# DRM-X_voice_split_resistors.net
KiCad netlist of a schematic drawn in EAGLE
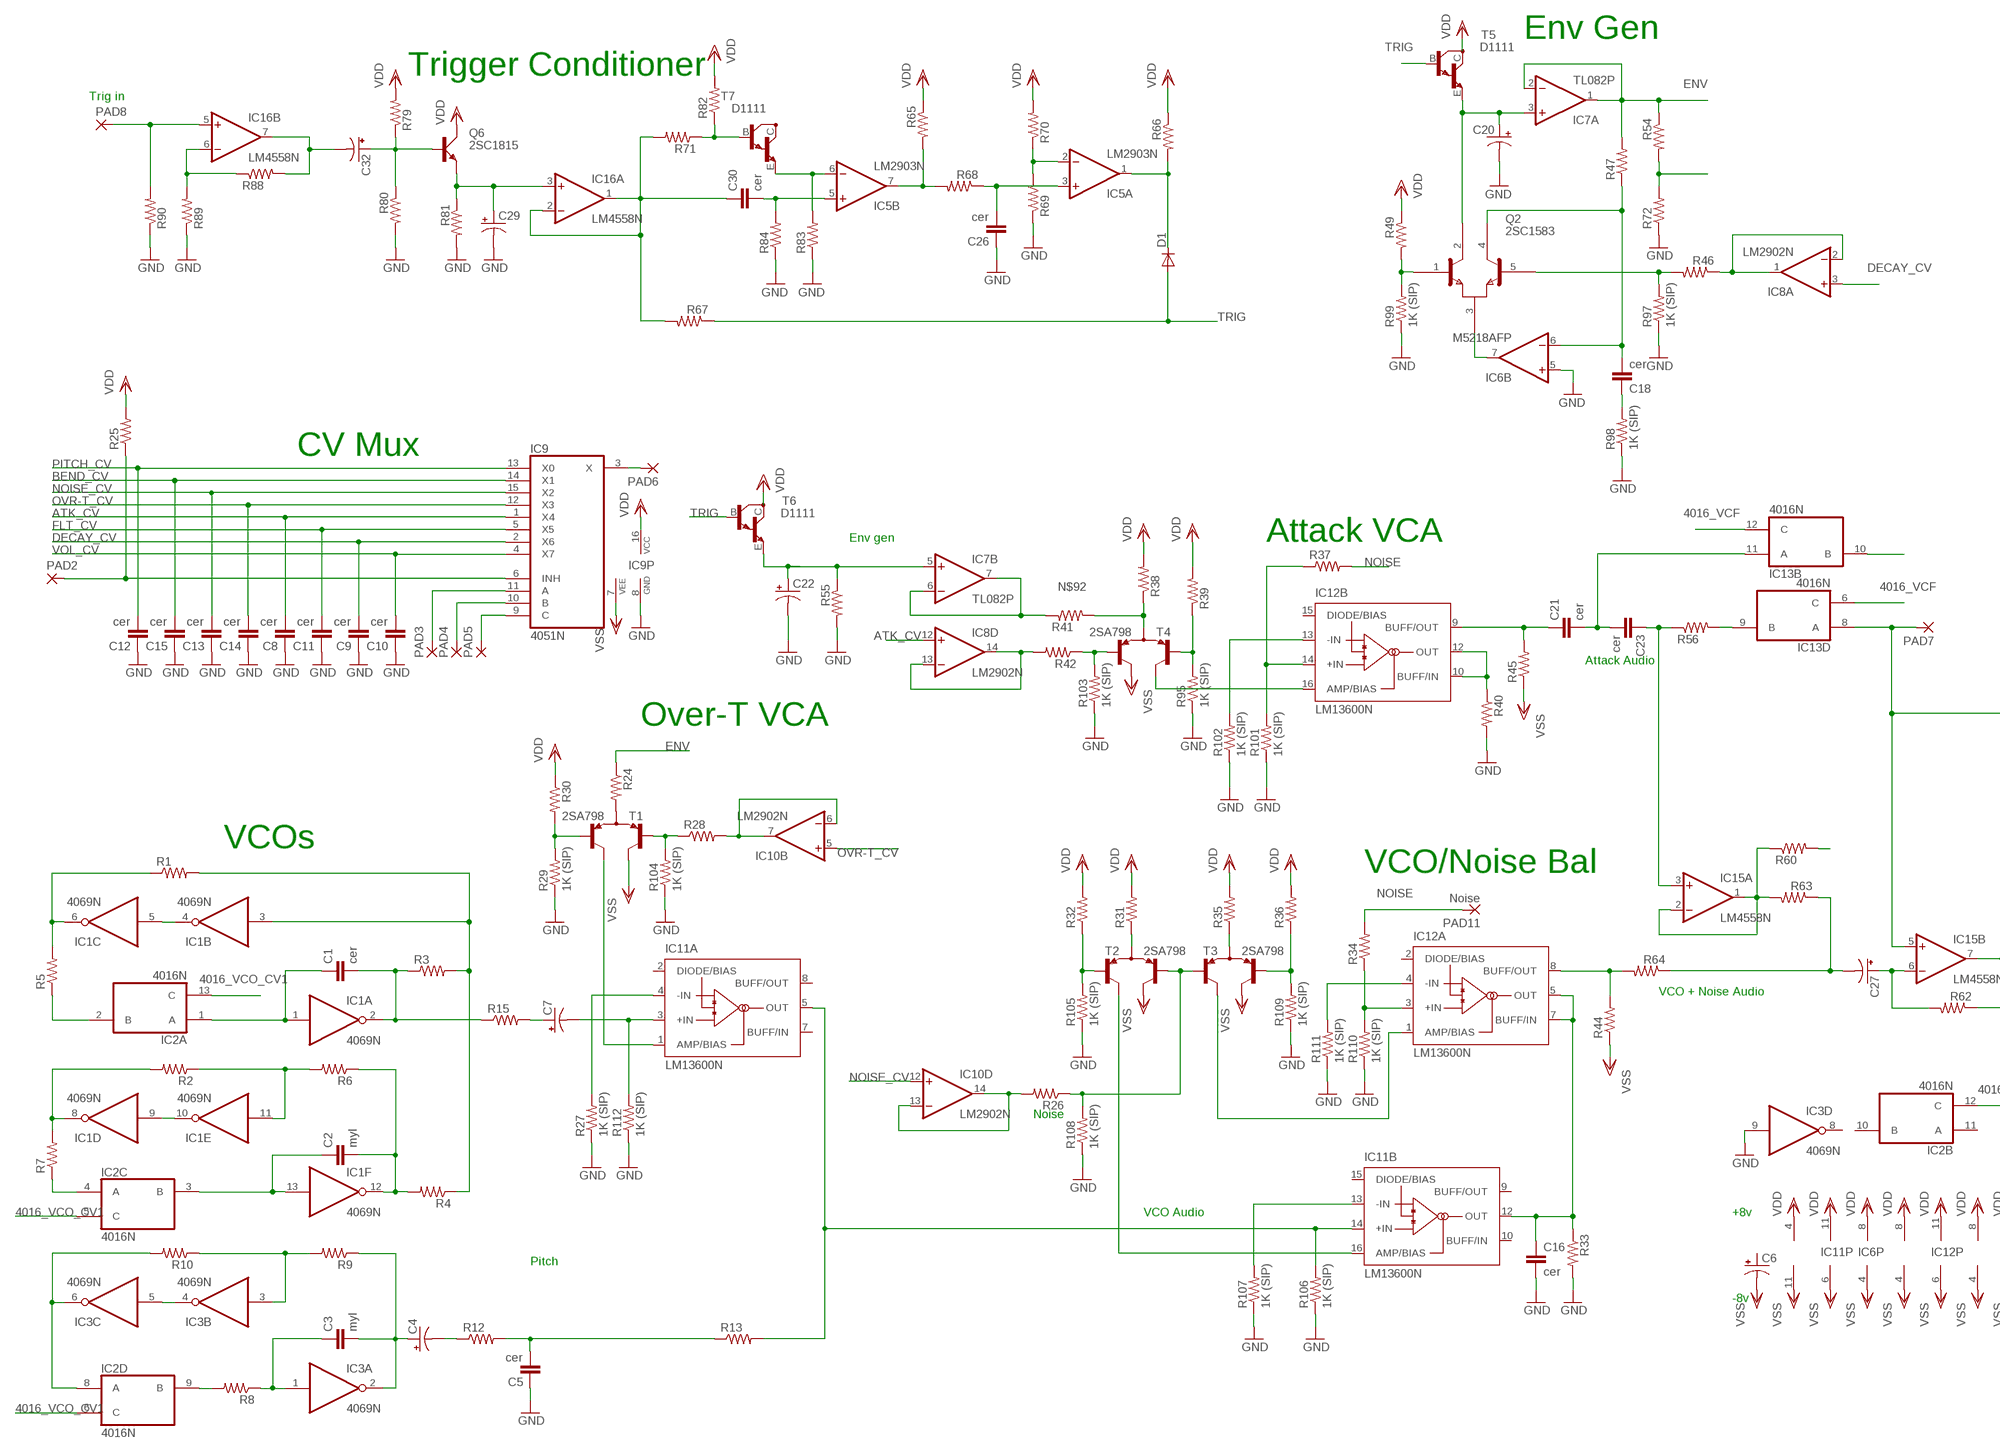
[diagram p0: schematic, sheet 1, part 1 of 2]
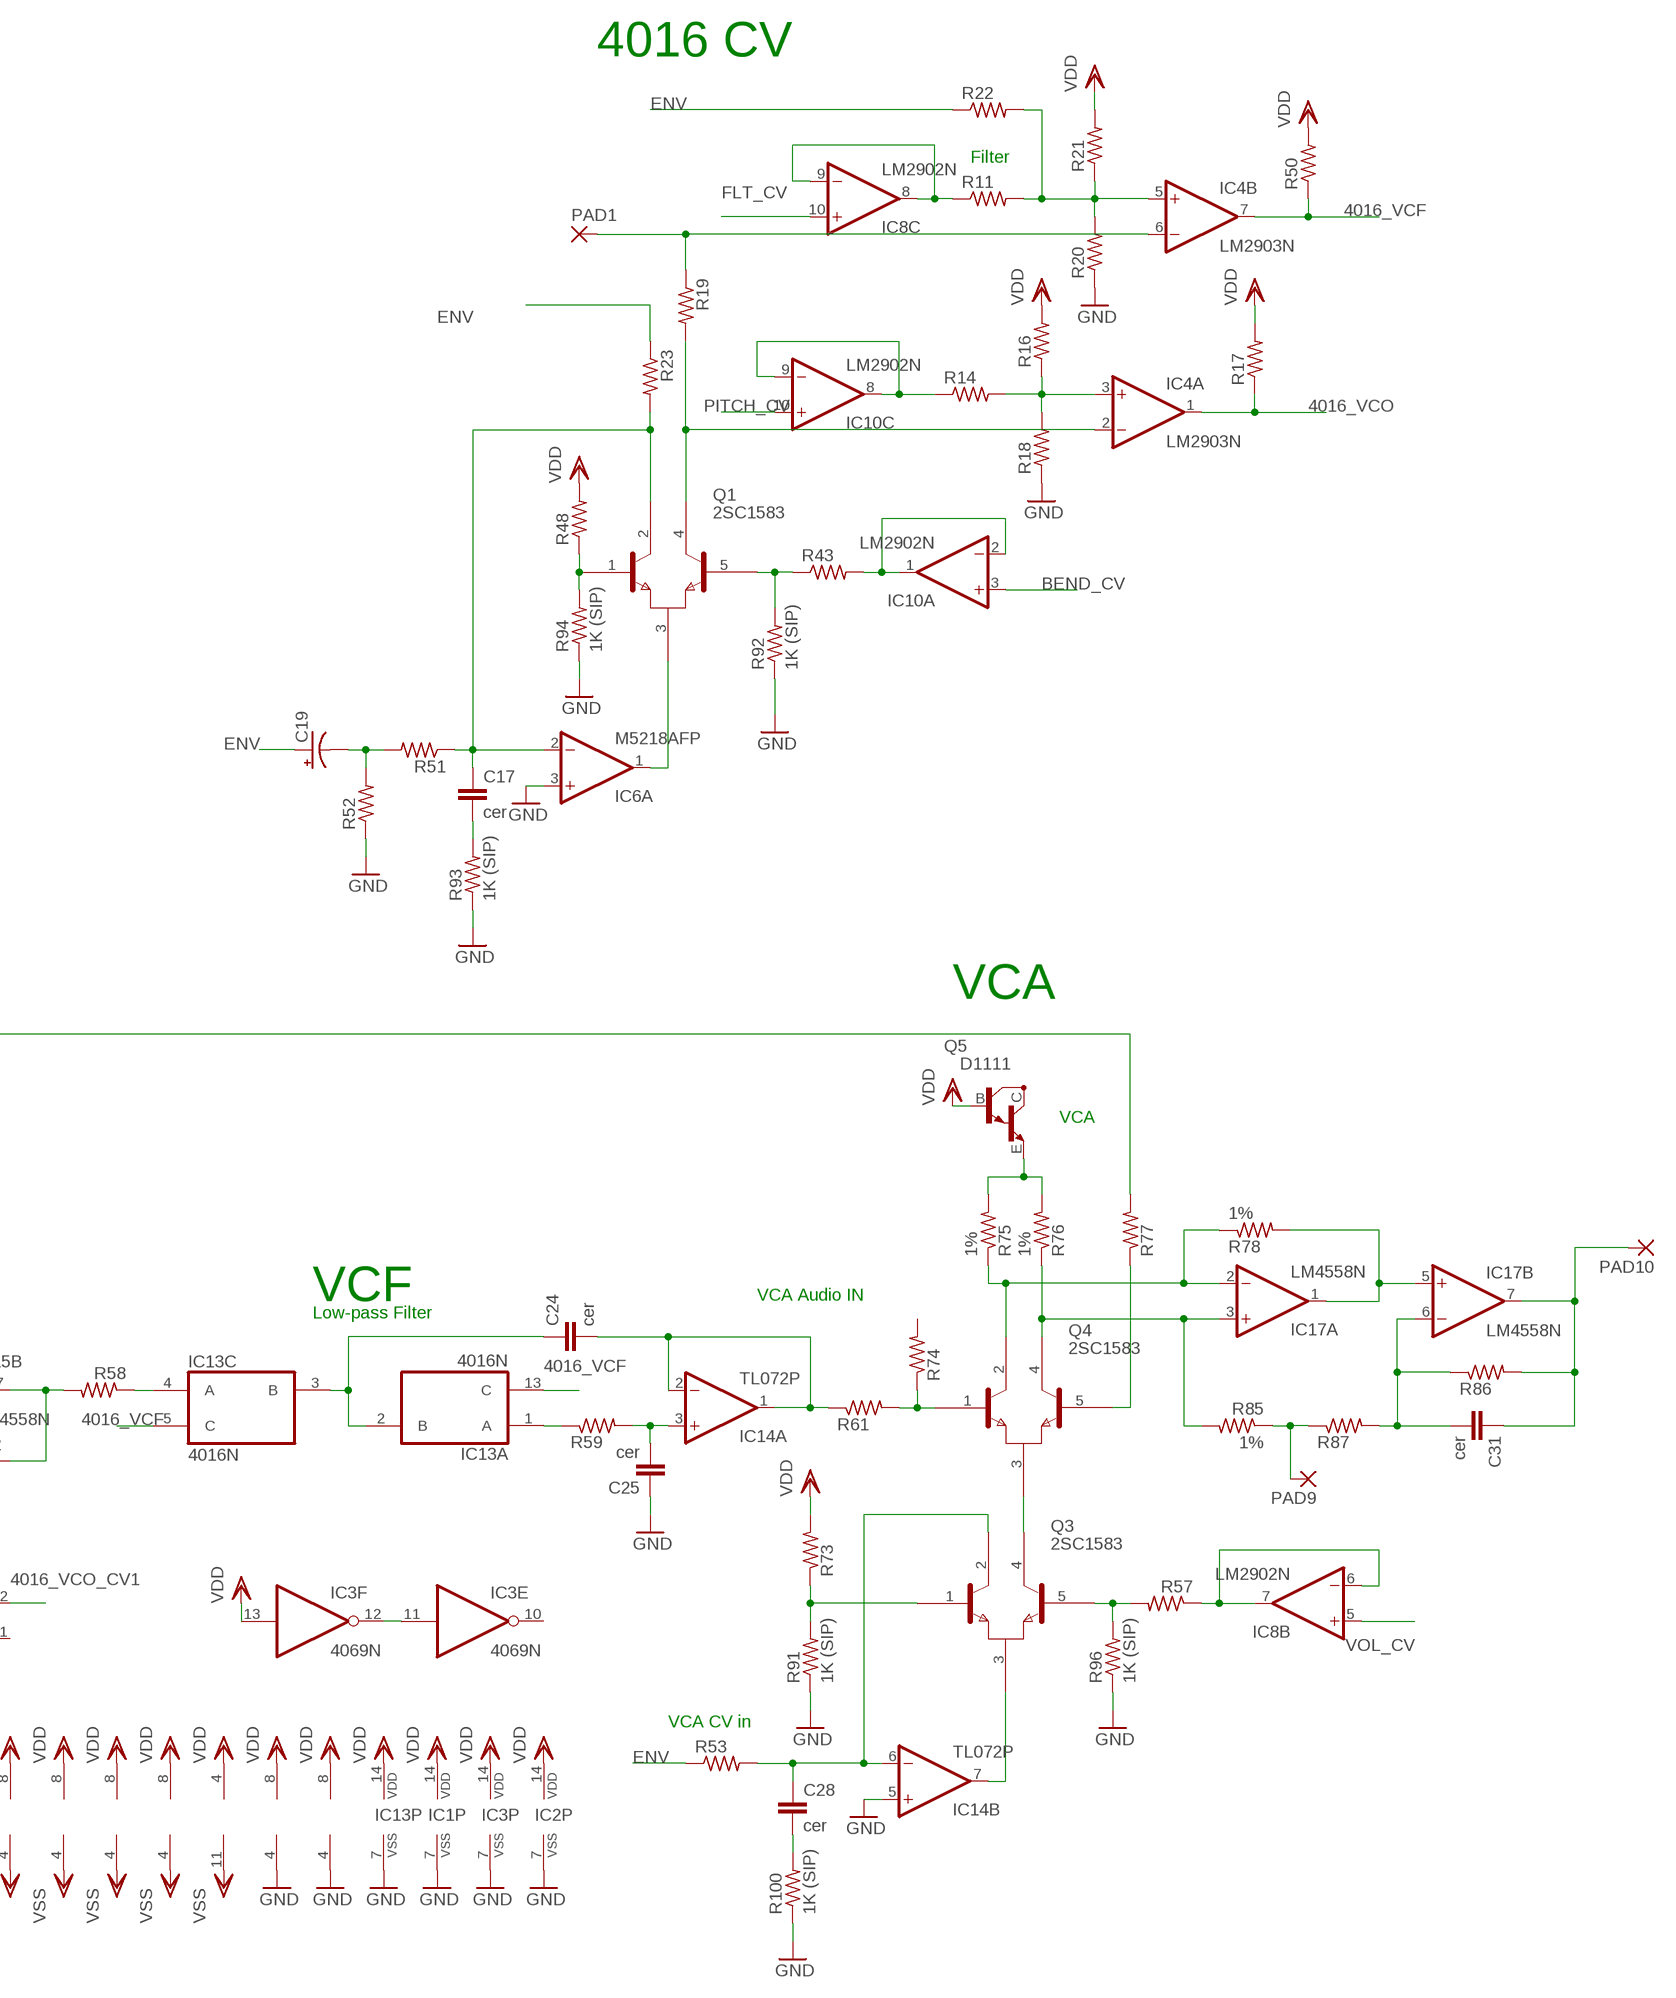
[diagram p1: schematic, sheet 1, part 2 of 2]

(export (version "E")
  (design (tool "Eeschema 10.0.6"))
  (components
    (comp (ref "C1")
      (value "cer")
      (footprint "eagle-import:C025-025X050")
      (libsource (lib "eagle-import") (part "C-EU025-025X050"))
    )
    (comp (ref "C2")
      (value "myl")
      (footprint "eagle-import:C025-024X044")
      (libsource (lib "eagle-import") (part "C-EU025-024X044"))
    )
    (comp (ref "C3")
      (value "myl")
      (footprint "eagle-import:C025-024X044")
      (libsource (lib "eagle-import") (part "C-EU025-024X044"))
    )
    (comp (ref "C4")
      (value "CPOL-USE2.5-5")
      (footprint "eagle-import:E2,5-5")
      (libsource (lib "eagle-import") (part "CPOL-USE2.5-5"))
    )
    (comp (ref "C5")
      (value "cer")
      (footprint "eagle-import:C025-025X050")
      (libsource (lib "eagle-import") (part "C-EU025-025X050"))
    )
    (comp (ref "C6")
      (value "CPOL-USE2.5-7")
      (footprint "eagle-import:E2,5-7")
      (libsource (lib "eagle-import") (part "CPOL-USE2.5-7"))
    )
    (comp (ref "C7")
      (value "CPOL-USE2.5-5")
      (footprint "eagle-import:E2,5-5")
      (libsource (lib "eagle-import") (part "CPOL-USE2.5-5"))
    )
    (comp (ref "C8")
      (value "cer")
      (footprint "eagle-import:C025-025X050")
      (libsource (lib "eagle-import") (part "C-EU025-025X050"))
    )
    (comp (ref "C9")
      (value "cer")
      (footprint "eagle-import:C025-025X050")
      (libsource (lib "eagle-import") (part "C-EU025-025X050"))
    )
    (comp (ref "C10")
      (value "cer")
      (footprint "eagle-import:C025-025X050")
      (libsource (lib "eagle-import") (part "C-EU025-025X050"))
    )
    (comp (ref "C11")
      (value "cer")
      (footprint "eagle-import:C025-025X050")
      (libsource (lib "eagle-import") (part "C-EU025-025X050"))
    )
    (comp (ref "C12")
      (value "cer")
      (footprint "eagle-import:C025-025X050")
      (libsource (lib "eagle-import") (part "C-EU025-025X050"))
    )
    (comp (ref "C13")
      (value "cer")
      (footprint "eagle-import:C025-025X050")
      (libsource (lib "eagle-import") (part "C-EU025-025X050"))
    )
    (comp (ref "C14")
      (value "cer")
      (footprint "eagle-import:C025-025X050")
      (libsource (lib "eagle-import") (part "C-EU025-025X050"))
    )
    (comp (ref "C15")
      (value "cer")
      (footprint "eagle-import:C025-025X050")
      (libsource (lib "eagle-import") (part "C-EU025-025X050"))
    )
    (comp (ref "C16")
      (value "cer")
      (footprint "eagle-import:C025-025X050")
      (libsource (lib "eagle-import") (part "C-EU025-025X050"))
    )
    (comp (ref "C17")
      (value "cer")
      (footprint "eagle-import:C025-025X050")
      (libsource (lib "eagle-import") (part "C-EU025-025X050"))
    )
    (comp (ref "C18")
      (value "cer")
      (footprint "eagle-import:C025-025X050")
      (libsource (lib "eagle-import") (part "C-EU025-025X050"))
    )
    (comp (ref "C19")
      (value "CPOL-USE2.5-5")
      (footprint "eagle-import:E2,5-5")
      (libsource (lib "eagle-import") (part "CPOL-USE2.5-5"))
    )
    (comp (ref "C20")
      (value "CPOL-USE2.5-5")
      (footprint "eagle-import:E2,5-5")
      (libsource (lib "eagle-import") (part "CPOL-USE2.5-5"))
    )
    (comp (ref "C21")
      (value "cer")
      (footprint "eagle-import:C025-025X050")
      (libsource (lib "eagle-import") (part "C-EU025-025X050"))
    )
    (comp (ref "C22")
      (value "CPOL-USE2.5-5")
      (footprint "eagle-import:E2,5-5")
      (libsource (lib "eagle-import") (part "CPOL-USE2.5-5"))
    )
    (comp (ref "C23")
      (value "cer")
      (footprint "eagle-import:C025-025X050")
      (libsource (lib "eagle-import") (part "C-EU025-025X050"))
    )
    (comp (ref "C24")
      (value "cer")
      (footprint "eagle-import:C025-025X050")
      (libsource (lib "eagle-import") (part "C-EU025-025X050"))
    )
    (comp (ref "C25")
      (value "cer")
      (footprint "eagle-import:C025-025X050")
      (libsource (lib "eagle-import") (part "C-EU025-025X050"))
    )
    (comp (ref "C26")
      (value "cer")
      (footprint "eagle-import:C025-025X050")
      (libsource (lib "eagle-import") (part "C-EU025-025X050"))
    )
    (comp (ref "C27")
      (value "CPOL-USE2.5-5")
      (footprint "eagle-import:E2,5-5")
      (libsource (lib "eagle-import") (part "CPOL-USE2.5-5"))
    )
    (comp (ref "C28")
      (value "cer")
      (footprint "eagle-import:C025-025X050")
      (libsource (lib "eagle-import") (part "C-EU025-025X050"))
    )
    (comp (ref "C29")
      (value "CPOL-USE2.5-5")
      (footprint "eagle-import:E2,5-5")
      (libsource (lib "eagle-import") (part "CPOL-USE2.5-5"))
    )
    (comp (ref "C30")
      (value "cer")
      (footprint "eagle-import:C025-025X050")
      (libsource (lib "eagle-import") (part "C-EU025-025X050"))
    )
    (comp (ref "C31")
      (value "cer")
      (footprint "eagle-import:C025-025X050")
      (libsource (lib "eagle-import") (part "C-EU025-025X050"))
    )
    (comp (ref "C32")
      (value "CPOL-USE2.5-5")
      (footprint "eagle-import:E2,5-5")
      (libsource (lib "eagle-import") (part "CPOL-USE2.5-5"))
    )
    (comp (ref "D1")
      (value "DIODE-D-5")
      (footprint "eagle-import:D-5")
      (libsource (lib "eagle-import") (part "DIODE-D-5"))
    )
    (comp (ref "IC1")
      (value "4069N")
      (footprint "eagle-import:DIL14")
      (libsource (lib "eagle-import") (part "4069N"))
    )
    (comp (ref "IC2")
      (value "4016N")
      (footprint "eagle-import:DIL14")
      (libsource (lib "eagle-import") (part "4016N"))
    )
    (comp (ref "IC3")
      (value "4069N")
      (footprint "eagle-import:DIL14")
      (libsource (lib "eagle-import") (part "4069N"))
    )
    (comp (ref "IC4")
      (value "LM2903N")
      (footprint "eagle-import:DIL08")
      (libsource (lib "eagle-import") (part "LM2903N"))
    )
    (comp (ref "IC5")
      (value "LM2903N")
      (footprint "eagle-import:DIL08")
      (libsource (lib "eagle-import") (part "LM2903N"))
    )
    (comp (ref "IC6")
      (value "M5218AFP")
      (footprint "eagle-import:SOP8")
      (libsource (lib "eagle-import") (part "M5218AFP"))
    )
    (comp (ref "IC7")
      (value "TL082P")
      (footprint "eagle-import:DIL08")
      (libsource (lib "eagle-import") (part "TL082P"))
    )
    (comp (ref "IC8")
      (value "LM2902N")
      (footprint "eagle-import:DIL14")
      (libsource (lib "eagle-import") (part "LM2902N"))
    )
    (comp (ref "IC9")
      (value "4051N")
      (footprint "eagle-import:DIL16")
      (libsource (lib "eagle-import") (part "4051N"))
    )
    (comp (ref "IC10")
      (value "LM2902N")
      (footprint "eagle-import:DIL14")
      (libsource (lib "eagle-import") (part "LM2902N"))
    )
    (comp (ref "IC11")
      (value "LM13600N")
      (footprint "eagle-import:DIL16")
      (libsource (lib "eagle-import") (part "LM13600N"))
    )
    (comp (ref "IC12")
      (value "LM13600N")
      (footprint "eagle-import:DIL16")
      (libsource (lib "eagle-import") (part "LM13600N"))
    )
    (comp (ref "IC13")
      (value "4016N")
      (footprint "eagle-import:DIL14")
      (libsource (lib "eagle-import") (part "4016N"))
    )
    (comp (ref "IC14")
      (value "TL072P")
      (footprint "eagle-import:DIL08")
      (libsource (lib "eagle-import") (part "TL072P"))
    )
    (comp (ref "IC15")
      (value "LM4558N")
      (footprint "eagle-import:DIL08")
      (libsource (lib "eagle-import") (part "4558NLM"))
    )
    (comp (ref "IC16")
      (value "LM4558N")
      (footprint "eagle-import:DIL08")
      (libsource (lib "eagle-import") (part "4558NLM"))
    )
    (comp (ref "IC17")
      (value "LM4558N")
      (footprint "eagle-import:DIL08")
      (libsource (lib "eagle-import") (part "4558NLM"))
    )
    (comp (ref "PAD1")
      (value "2,0/0,9-O")
      (footprint "eagle-import:2,0_0,9-O")
      (libsource (lib "eagle-import") (part "2,0/0,9-O"))
    )
    (comp (ref "PAD2")
      (value "2,0/0,9-O")
      (footprint "eagle-import:2,0_0,9-O")
      (libsource (lib "eagle-import") (part "2,0/0,9-O"))
    )
    (comp (ref "PAD3")
      (value "2,0/0,9-O")
      (footprint "eagle-import:2,0_0,9-O")
      (libsource (lib "eagle-import") (part "2,0/0,9-O"))
    )
    (comp (ref "PAD4")
      (value "2,0/0,9-O")
      (footprint "eagle-import:2,0_0,9-O")
      (libsource (lib "eagle-import") (part "2,0/0,9-O"))
    )
    (comp (ref "PAD5")
      (value "2,0/0,9-O")
      (footprint "eagle-import:2,0_0,9-O")
      (libsource (lib "eagle-import") (part "2,0/0,9-O"))
    )
    (comp (ref "PAD6")
      (value "2,0/0,9-O")
      (footprint "eagle-import:2,0_0,9-O")
      (libsource (lib "eagle-import") (part "2,0/0,9-O"))
    )
    (comp (ref "PAD7")
      (value "2,0/0,9-O")
      (footprint "eagle-import:2,0_0,9-O")
      (libsource (lib "eagle-import") (part "2,0/0,9-O"))
    )
    (comp (ref "PAD8")
      (value "2,0/0,9-O")
      (footprint "eagle-import:2,0_0,9-O")
      (libsource (lib "eagle-import") (part "2,0/0,9-O"))
    )
    (comp (ref "PAD9")
      (value "2,0/0,9-O")
      (footprint "eagle-import:2,0_0,9-O")
      (libsource (lib "eagle-import") (part "2,0/0,9-O"))
    )
    (comp (ref "PAD10")
      (value "2,0/0,9-O")
      (footprint "eagle-import:2,0_0,9-O")
      (libsource (lib "eagle-import") (part "2,0/0,9-O"))
    )
    (comp (ref "PAD11")
      (value "Noise")
      (footprint "eagle-import:2,0_0,9-O")
      (libsource (lib "eagle-import") (part "2,0/0,9-O"))
    )
    (comp (ref "Q1")
      (value "2SC1583")
      (footprint "eagle-import:XSIST_SIP5")
      (libsource (lib "eagle-import") (part "2SC1583"))
    )
    (comp (ref "Q2")
      (value "2SC1583")
      (footprint "eagle-import:XSIST_SIP5")
      (libsource (lib "eagle-import") (part "2SC1583"))
    )
    (comp (ref "Q3")
      (value "2SC1583")
      (footprint "eagle-import:XSIST_SIP5")
      (libsource (lib "eagle-import") (part "2SC1583"))
    )
    (comp (ref "Q4")
      (value "2SC1583")
      (footprint "eagle-import:XSIST_SIP5")
      (libsource (lib "eagle-import") (part "2SC1583"))
    )
    (comp (ref "Q5")
      (value "D1111")
      (footprint "eagle-import:TO92-ECB")
      (libsource (lib "eagle-import") (part "BC517D1111-ECB"))
    )
    (comp (ref "Q6")
      (value "2SC1815")
      (footprint "eagle-import:TO92-LINE")
      (libsource (lib "eagle-import") (part "2SC1815"))
    )
    (comp (ref "R1")
      (value "R-US_0204/7")
      (footprint "eagle-import:0204_7")
      (libsource (lib "eagle-import") (part "R-US_0204/7"))
    )
    (comp (ref "R2")
      (value "R-US_0204/7")
      (footprint "eagle-import:0204_7")
      (libsource (lib "eagle-import") (part "R-US_0204/7"))
    )
    (comp (ref "R3")
      (value "R-US_0204/7")
      (footprint "eagle-import:0204_7")
      (libsource (lib "eagle-import") (part "R-US_0204/7"))
    )
    (comp (ref "R4")
      (value "R-US_0204/7")
      (footprint "eagle-import:0204_7")
      (libsource (lib "eagle-import") (part "R-US_0204/7"))
    )
    (comp (ref "R5")
      (value "R-US_0204/7")
      (footprint "eagle-import:0204_7")
      (libsource (lib "eagle-import") (part "R-US_0204/7"))
    )
    (comp (ref "R6")
      (value "R-US_0204/7")
      (footprint "eagle-import:0204_7")
      (libsource (lib "eagle-import") (part "R-US_0204/7"))
    )
    (comp (ref "R7")
      (value "R-US_0204/7")
      (footprint "eagle-import:0204_7")
      (libsource (lib "eagle-import") (part "R-US_0204/7"))
    )
    (comp (ref "R8")
      (value "R-US_0204/7")
      (footprint "eagle-import:0204_7")
      (libsource (lib "eagle-import") (part "R-US_0204/7"))
    )
    (comp (ref "R9")
      (value "R-US_0204/7")
      (footprint "eagle-import:0204_7")
      (libsource (lib "eagle-import") (part "R-US_0204/7"))
    )
    (comp (ref "R10")
      (value "R-US_0204/7")
      (footprint "eagle-import:0204_7")
      (libsource (lib "eagle-import") (part "R-US_0204/7"))
    )
    (comp (ref "R11")
      (value "R-US_0204/7")
      (footprint "eagle-import:0204_7")
      (libsource (lib "eagle-import") (part "R-US_0204/7"))
    )
    (comp (ref "R12")
      (value "R-US_0204/7")
      (footprint "eagle-import:0204_7")
      (libsource (lib "eagle-import") (part "R-US_0204/7"))
    )
    (comp (ref "R13")
      (value "R-US_0204/7")
      (footprint "eagle-import:0204_7")
      (libsource (lib "eagle-import") (part "R-US_0204/7"))
    )
    (comp (ref "R14")
      (value "R-US_0204/7")
      (footprint "eagle-import:0204_7")
      (libsource (lib "eagle-import") (part "R-US_0204/7"))
    )
    (comp (ref "R15")
      (value "R-US_0204/7")
      (footprint "eagle-import:0204_7")
      (libsource (lib "eagle-import") (part "R-US_0204/7"))
    )
    (comp (ref "R16")
      (value "R-US_0204/7")
      (footprint "eagle-import:0204_7")
      (libsource (lib "eagle-import") (part "R-US_0204/7"))
    )
    (comp (ref "R17")
      (value "R-US_0204/7")
      (footprint "eagle-import:0204_7")
      (libsource (lib "eagle-import") (part "R-US_0204/7"))
    )
    (comp (ref "R18")
      (value "R-US_0204/7")
      (footprint "eagle-import:0204_7")
      (libsource (lib "eagle-import") (part "R-US_0204/7"))
    )
    (comp (ref "R19")
      (value "R-US_0204/7")
      (footprint "eagle-import:0204_7")
      (libsource (lib "eagle-import") (part "R-US_0204/7"))
    )
    (comp (ref "R20")
      (value "R-US_0204/7")
      (footprint "eagle-import:0204_7")
      (libsource (lib "eagle-import") (part "R-US_0204/7"))
    )
    (comp (ref "R21")
      (value "R-US_0204/7")
      (footprint "eagle-import:0204_7")
      (libsource (lib "eagle-import") (part "R-US_0204/7"))
    )
    (comp (ref "R22")
      (value "R-US_0204/7")
      (footprint "eagle-import:0204_7")
      (libsource (lib "eagle-import") (part "R-US_0204/7"))
    )
    (comp (ref "R23")
      (value "R-US_0204/7")
      (footprint "eagle-import:0204_7")
      (libsource (lib "eagle-import") (part "R-US_0204/7"))
    )
    (comp (ref "R24")
      (value "R-US_0204/7")
      (footprint "eagle-import:0204_7")
      (libsource (lib "eagle-import") (part "R-US_0204/7"))
    )
    (comp (ref "R25")
      (value "R-US_0204/7")
      (footprint "eagle-import:0204_7")
      (libsource (lib "eagle-import") (part "R-US_0204/7"))
    )
    (comp (ref "R26")
      (value "R-US_0204/7")
      (footprint "eagle-import:0204_7")
      (libsource (lib "eagle-import") (part "R-US_0204/7"))
    )
    (comp (ref "R27")
      (value "1K (SIP)")
      (footprint "eagle-import:0204_7")
      (libsource (lib "eagle-import") (part "R-US_0204/7"))
    )
    (comp (ref "R28")
      (value "R-US_0204/7")
      (footprint "eagle-import:0204_7")
      (libsource (lib "eagle-import") (part "R-US_0204/7"))
    )
    (comp (ref "R29")
      (value "1K (SIP)")
      (footprint "eagle-import:0204_7")
      (libsource (lib "eagle-import") (part "R-US_0204/7"))
    )
    (comp (ref "R30")
      (value "R-US_0204/7")
      (footprint "eagle-import:0204_7")
      (libsource (lib "eagle-import") (part "R-US_0204/7"))
    )
    (comp (ref "R31")
      (value "R-US_0204/7")
      (footprint "eagle-import:0204_7")
      (libsource (lib "eagle-import") (part "R-US_0204/7"))
    )
    (comp (ref "R32")
      (value "R-US_0204/7")
      (footprint "eagle-import:0204_7")
      (libsource (lib "eagle-import") (part "R-US_0204/7"))
    )
    (comp (ref "R33")
      (value "R-US_0204/7")
      (footprint "eagle-import:0204_7")
      (libsource (lib "eagle-import") (part "R-US_0204/7"))
    )
    (comp (ref "R34")
      (value "R-US_0204/7")
      (footprint "eagle-import:0204_7")
      (libsource (lib "eagle-import") (part "R-US_0204/7"))
    )
    (comp (ref "R35")
      (value "R-US_0204/7")
      (footprint "eagle-import:0204_7")
      (libsource (lib "eagle-import") (part "R-US_0204/7"))
    )
    (comp (ref "R36")
      (value "R-US_0204/7")
      (footprint "eagle-import:0204_7")
      (libsource (lib "eagle-import") (part "R-US_0204/7"))
    )
    (comp (ref "R37")
      (value "R-US_0204/7")
      (footprint "eagle-import:0204_7")
      (libsource (lib "eagle-import") (part "R-US_0204/7"))
    )
    (comp (ref "R38")
      (value "R-US_0204/7")
      (footprint "eagle-import:0204_7")
      (libsource (lib "eagle-import") (part "R-US_0204/7"))
    )
    (comp (ref "R39")
      (value "R-US_0204/7")
      (footprint "eagle-import:0204_7")
      (libsource (lib "eagle-import") (part "R-US_0204/7"))
    )
    (comp (ref "R40")
      (value "R-US_0204/7")
      (footprint "eagle-import:0204_7")
      (libsource (lib "eagle-import") (part "R-US_0204/7"))
    )
    (comp (ref "R41")
      (value "R-US_0204/7")
      (footprint "eagle-import:0204_7")
      (libsource (lib "eagle-import") (part "R-US_0204/7"))
    )
    (comp (ref "R42")
      (value "R-US_0204/7")
      (footprint "eagle-import:0204_7")
      (libsource (lib "eagle-import") (part "R-US_0204/7"))
    )
    (comp (ref "R43")
      (value "R-US_0204/7")
      (footprint "eagle-import:0204_7")
      (libsource (lib "eagle-import") (part "R-US_0204/7"))
    )
    (comp (ref "R44")
      (value "R-US_0204/7")
      (footprint "eagle-import:0204_7")
      (libsource (lib "eagle-import") (part "R-US_0204/7"))
    )
    (comp (ref "R45")
      (value "R-US_0204/7")
      (footprint "eagle-import:0204_7")
      (libsource (lib "eagle-import") (part "R-US_0204/7"))
    )
    (comp (ref "R46")
      (value "R-US_0204/7")
      (footprint "eagle-import:0204_7")
      (libsource (lib "eagle-import") (part "R-US_0204/7"))
    )
    (comp (ref "R47")
      (value "R-US_0204/7")
      (footprint "eagle-import:0204_7")
      (libsource (lib "eagle-import") (part "R-US_0204/7"))
    )
    (comp (ref "R48")
      (value "R-US_0204/7")
      (footprint "eagle-import:0204_7")
      (libsource (lib "eagle-import") (part "R-US_0204/7"))
    )
    (comp (ref "R49")
      (value "R-US_0204/7")
      (footprint "eagle-import:0204_7")
      (libsource (lib "eagle-import") (part "R-US_0204/7"))
    )
    (comp (ref "R50")
      (value "R-US_0204/7")
      (footprint "eagle-import:0204_7")
      (libsource (lib "eagle-import") (part "R-US_0204/7"))
    )
    (comp (ref "R51")
      (value "R-US_0204/7")
      (footprint "eagle-import:0204_7")
      (libsource (lib "eagle-import") (part "R-US_0204/7"))
    )
    (comp (ref "R52")
      (value "R-US_0204/7")
      (footprint "eagle-import:0204_7")
      (libsource (lib "eagle-import") (part "R-US_0204/7"))
    )
    (comp (ref "R53")
      (value "R-US_0204/7")
      (footprint "eagle-import:0204_7")
      (libsource (lib "eagle-import") (part "R-US_0204/7"))
    )
    (comp (ref "R54")
      (value "R-US_0204/7")
      (footprint "eagle-import:0204_7")
      (libsource (lib "eagle-import") (part "R-US_0204/7"))
    )
    (comp (ref "R55")
      (value "R-US_0204/7")
      (footprint "eagle-import:0204_7")
      (libsource (lib "eagle-import") (part "R-US_0204/7"))
    )
    (comp (ref "R56")
      (value "R-US_0204/7")
      (footprint "eagle-import:0204_7")
      (libsource (lib "eagle-import") (part "R-US_0204/7"))
    )
    (comp (ref "R57")
      (value "R-US_0204/7")
      (footprint "eagle-import:0204_7")
      (libsource (lib "eagle-import") (part "R-US_0204/7"))
    )
    (comp (ref "R58")
      (value "R-US_0204/7")
      (footprint "eagle-import:0204_7")
      (libsource (lib "eagle-import") (part "R-US_0204/7"))
    )
    (comp (ref "R59")
      (value "R-US_0204/7")
      (footprint "eagle-import:0204_7")
      (libsource (lib "eagle-import") (part "R-US_0204/7"))
    )
    (comp (ref "R60")
      (value "R-US_0204/7")
      (footprint "eagle-import:0204_7")
      (libsource (lib "eagle-import") (part "R-US_0204/7"))
    )
    (comp (ref "R61")
      (value "R-US_0204/7")
      (footprint "eagle-import:0204_7")
      (libsource (lib "eagle-import") (part "R-US_0204/7"))
    )
    (comp (ref "R62")
      (value "R-US_0204/7")
      (footprint "eagle-import:0204_7")
      (libsource (lib "eagle-import") (part "R-US_0204/7"))
    )
    (comp (ref "R63")
      (value "R-US_0204/7")
      (footprint "eagle-import:0204_7")
      (libsource (lib "eagle-import") (part "R-US_0204/7"))
    )
    (comp (ref "R64")
      (value "R-US_0204/7")
      (footprint "eagle-import:0204_7")
      (libsource (lib "eagle-import") (part "R-US_0204/7"))
    )
    (comp (ref "R65")
      (value "R-US_0204/7")
      (footprint "eagle-import:0204_7")
      (libsource (lib "eagle-import") (part "R-US_0204/7"))
    )
    (comp (ref "R66")
      (value "R-US_0204/7")
      (footprint "eagle-import:0204_7")
      (libsource (lib "eagle-import") (part "R-US_0204/7"))
    )
    (comp (ref "R67")
      (value "R-US_0204/7")
      (footprint "eagle-import:0204_7")
      (libsource (lib "eagle-import") (part "R-US_0204/7"))
    )
    (comp (ref "R68")
      (value "R-US_0204/7")
      (footprint "eagle-import:0204_7")
      (libsource (lib "eagle-import") (part "R-US_0204/7"))
    )
    (comp (ref "R69")
      (value "R-US_0204/7")
      (footprint "eagle-import:0204_7")
      (libsource (lib "eagle-import") (part "R-US_0204/7"))
    )
    (comp (ref "R70")
      (value "R-US_0204/7")
      (footprint "eagle-import:0204_7")
      (libsource (lib "eagle-import") (part "R-US_0204/7"))
    )
    (comp (ref "R71")
      (value "R-US_0204/7")
      (footprint "eagle-import:0204_7")
      (libsource (lib "eagle-import") (part "R-US_0204/7"))
    )
    (comp (ref "R72")
      (value "R-US_0204/7")
      (footprint "eagle-import:0204_7")
      (libsource (lib "eagle-import") (part "R-US_0204/7"))
    )
    (comp (ref "R73")
      (value "R-US_0204/7")
      (footprint "eagle-import:0204_7")
      (libsource (lib "eagle-import") (part "R-US_0204/7"))
    )
    (comp (ref "R74")
      (value "R-US_0204/7")
      (footprint "eagle-import:0204_7")
      (libsource (lib "eagle-import") (part "R-US_0204/7"))
    )
    (comp (ref "R75")
      (value "1%")
      (footprint "eagle-import:0204_7")
      (libsource (lib "eagle-import") (part "R-US_0204/7"))
    )
    (comp (ref "R76")
      (value "1%")
      (footprint "eagle-import:0204_7")
      (libsource (lib "eagle-import") (part "R-US_0204/7"))
    )
    (comp (ref "R77")
      (value "R-US_0204/7")
      (footprint "eagle-import:0204_7")
      (libsource (lib "eagle-import") (part "R-US_0204/7"))
    )
    (comp (ref "R78")
      (value "1%")
      (footprint "eagle-import:0204_7")
      (libsource (lib "eagle-import") (part "R-US_0204/7"))
    )
    (comp (ref "R79")
      (value "R-US_0204/7")
      (footprint "eagle-import:0204_7")
      (libsource (lib "eagle-import") (part "R-US_0204/7"))
    )
    (comp (ref "R80")
      (value "R-US_0204/7")
      (footprint "eagle-import:0204_7")
      (libsource (lib "eagle-import") (part "R-US_0204/7"))
    )
    (comp (ref "R81")
      (value "R-US_0204/7")
      (footprint "eagle-import:0204_7")
      (libsource (lib "eagle-import") (part "R-US_0204/7"))
    )
    (comp (ref "R82")
      (value "R-US_0204/7")
      (footprint "eagle-import:0204_7")
      (libsource (lib "eagle-import") (part "R-US_0204/7"))
    )
    (comp (ref "R83")
      (value "R-US_0204/7")
      (footprint "eagle-import:0204_7")
      (libsource (lib "eagle-import") (part "R-US_0204/7"))
    )
    (comp (ref "R84")
      (value "R-US_0204/7")
      (footprint "eagle-import:0204_7")
      (libsource (lib "eagle-import") (part "R-US_0204/7"))
    )
    (comp (ref "R85")
      (value "1%")
      (footprint "eagle-import:0204_7")
      (libsource (lib "eagle-import") (part "R-US_0204/7"))
    )
    (comp (ref "R86")
      (value "R-US_0204/7")
      (footprint "eagle-import:0204_7")
      (libsource (lib "eagle-import") (part "R-US_0204/7"))
    )
    (comp (ref "R87")
      (value "R-US_0204/7")
      (footprint "eagle-import:0204_7")
      (libsource (lib "eagle-import") (part "R-US_0204/7"))
    )
    (comp (ref "R88")
      (value "R-US_0204/7")
      (footprint "eagle-import:0204_7")
      (libsource (lib "eagle-import") (part "R-US_0204/7"))
    )
    (comp (ref "R89")
      (value "R-US_0204/7")
      (footprint "eagle-import:0204_7")
      (libsource (lib "eagle-import") (part "R-US_0204/7"))
    )
    (comp (ref "R90")
      (value "R-US_0204/7")
      (footprint "eagle-import:0204_7")
      (libsource (lib "eagle-import") (part "R-US_0204/7"))
    )
    (comp (ref "R91")
      (value "1K (SIP)")
      (footprint "eagle-import:0204_7")
      (libsource (lib "eagle-import") (part "R-US_0204/7"))
    )
    (comp (ref "R92")
      (value "1K (SIP)")
      (footprint "eagle-import:0204_7")
      (libsource (lib "eagle-import") (part "R-US_0204/7"))
    )
    (comp (ref "R93")
      (value "1K (SIP)")
      (footprint "eagle-import:0204_7")
      (libsource (lib "eagle-import") (part "R-US_0204/7"))
    )
    (comp (ref "R94")
      (value "1K (SIP)")
      (footprint "eagle-import:0204_7")
      (libsource (lib "eagle-import") (part "R-US_0204/7"))
    )
    (comp (ref "R95")
      (value "1K (SIP)")
      (footprint "eagle-import:0204_7")
      (libsource (lib "eagle-import") (part "R-US_0204/7"))
    )
    (comp (ref "R96")
      (value "1K (SIP)")
      (footprint "eagle-import:0204_7")
      (libsource (lib "eagle-import") (part "R-US_0204/7"))
    )
    (comp (ref "R97")
      (value "1K (SIP)")
      (footprint "eagle-import:0204_7")
      (libsource (lib "eagle-import") (part "R-US_0204/7"))
    )
    (comp (ref "R98")
      (value "1K (SIP)")
      (footprint "eagle-import:0204_7")
      (libsource (lib "eagle-import") (part "R-US_0204/7"))
    )
    (comp (ref "R99")
      (value "1K (SIP)")
      (footprint "eagle-import:0204_7")
      (libsource (lib "eagle-import") (part "R-US_0204/7"))
    )
    (comp (ref "R100")
      (value "1K (SIP)")
      (footprint "eagle-import:0204_7")
      (libsource (lib "eagle-import") (part "R-US_0204/7"))
    )
    (comp (ref "R101")
      (value "1K (SIP)")
      (footprint "eagle-import:0204_7")
      (libsource (lib "eagle-import") (part "R-US_0204/7"))
    )
    (comp (ref "R102")
      (value "1K (SIP)")
      (footprint "eagle-import:0204_7")
      (libsource (lib "eagle-import") (part "R-US_0204/7"))
    )
    (comp (ref "R103")
      (value "1K (SIP)")
      (footprint "eagle-import:0204_7")
      (libsource (lib "eagle-import") (part "R-US_0204/7"))
    )
    (comp (ref "R104")
      (value "1K (SIP)")
      (footprint "eagle-import:0204_7")
      (libsource (lib "eagle-import") (part "R-US_0204/7"))
    )
    (comp (ref "R105")
      (value "1K (SIP)")
      (footprint "eagle-import:0204_7")
      (libsource (lib "eagle-import") (part "R-US_0204/7"))
    )
    (comp (ref "R106")
      (value "1K (SIP)")
      (footprint "eagle-import:0204_7")
      (libsource (lib "eagle-import") (part "R-US_0204/7"))
    )
    (comp (ref "R107")
      (value "1K (SIP)")
      (footprint "eagle-import:0204_7")
      (libsource (lib "eagle-import") (part "R-US_0204/7"))
    )
    (comp (ref "R108")
      (value "1K (SIP)")
      (footprint "eagle-import:0204_7")
      (libsource (lib "eagle-import") (part "R-US_0204/7"))
    )
    (comp (ref "R109")
      (value "1K (SIP)")
      (footprint "eagle-import:0204_7")
      (libsource (lib "eagle-import") (part "R-US_0204/7"))
    )
    (comp (ref "R110")
      (value "1K (SIP)")
      (footprint "eagle-import:0204_7")
      (libsource (lib "eagle-import") (part "R-US_0204/7"))
    )
    (comp (ref "R111")
      (value "1K (SIP)")
      (footprint "eagle-import:0204_7")
      (libsource (lib "eagle-import") (part "R-US_0204/7"))
    )
    (comp (ref "R112")
      (value "1K (SIP)")
      (footprint "eagle-import:0204_7")
      (libsource (lib "eagle-import") (part "R-US_0204/7"))
    )
    (comp (ref "T1")
      (value "2SA798")
      (footprint "eagle-import:SIP-5")
      (libsource (lib "eagle-import") (part "2SA798"))
    )
    (comp (ref "T2")
      (value "2SA798")
      (footprint "eagle-import:SIP-5")
      (libsource (lib "eagle-import") (part "2SA798"))
    )
    (comp (ref "T3")
      (value "2SA798")
      (footprint "eagle-import:SIP-5")
      (libsource (lib "eagle-import") (part "2SA798"))
    )
    (comp (ref "T4")
      (value "2SA798")
      (footprint "eagle-import:SIP-5")
      (libsource (lib "eagle-import") (part "2SA798"))
    )
    (comp (ref "T5")
      (value "D1111")
      (footprint "eagle-import:TO92-ECB")
      (libsource (lib "eagle-import") (part "BC517D1111-ECB"))
    )
    (comp (ref "T6")
      (value "D1111")
      (footprint "eagle-import:TO92-ECB")
      (libsource (lib "eagle-import") (part "BC517D1111-ECB"))
    )
    (comp (ref "T7")
      (value "D1111")
      (footprint "eagle-import:TO92-ECB")
      (libsource (lib "eagle-import") (part "BC517D1111-ECB"))
    )
  )
  (nets
    (net (code "1") (name "/4016_VCF") (class "Default")
      (node (ref "IC13") (pin "12") (pinfunction "C_12") (pintype "input"))
      (node (ref "IC13") (pin "13") (pinfunction "C_13") (pintype "input"))
      (node (ref "IC13") (pin "5") (pinfunction "C_5") (pintype "input"))
      (node (ref "IC13") (pin "6") (pinfunction "C_6") (pintype "input"))
      (node (ref "IC4") (pin "7") (pinfunction "OUT_7") (pintype "output"))
      (node (ref "R50") (pin "1") (pinfunction "1_1") (pintype "passive"))
    )
    (net (code "2") (name "/4016_VCO") (class "Default")
      (node (ref "IC4") (pin "1") (pinfunction "OUT_1") (pintype "output"))
      (node (ref "R17") (pin "1") (pinfunction "1_1") (pintype "passive"))
    )
    (net (code "3") (name "/4016_VCO_CV1") (class "Default")
      (node (ref "IC2") (pin "12") (pinfunction "C_12") (pintype "input"))
      (node (ref "IC2") (pin "13") (pinfunction "C_13") (pintype "input"))
      (node (ref "IC2") (pin "5") (pinfunction "C_5") (pintype "input"))
      (node (ref "IC2") (pin "6") (pinfunction "C_6") (pintype "input"))
    )
    (net (code "4") (name "/ATK_CV") (class "Default")
      (node (ref "C8") (pin "2") (pinfunction "2_2") (pintype "passive"))
      (node (ref "IC8") (pin "12") (pinfunction "+IN_12") (pintype "input"))
      (node (ref "IC9") (pin "1") (pinfunction "X4_1") (pintype "bidirectional"))
    )
    (net (code "5") (name "/BEND_CV") (class "Default")
      (node (ref "C15") (pin "2") (pinfunction "2_2") (pintype "passive"))
      (node (ref "IC10") (pin "3") (pinfunction "+IN_3") (pintype "input"))
      (node (ref "IC9") (pin "14") (pinfunction "X1_14") (pintype "bidirectional"))
    )
    (net (code "6") (name "/DECAY_CV") (class "Default")
      (node (ref "C9") (pin "2") (pinfunction "2_2") (pintype "passive"))
      (node (ref "IC8") (pin "3") (pinfunction "+IN_3") (pintype "input"))
      (node (ref "IC9") (pin "2") (pinfunction "X6_2") (pintype "bidirectional"))
    )
    (net (code "7") (name "/ENV") (class "Default")
      (node (ref "C19") (pin "+") (pinfunction "+_+") (pintype "passive"))
      (node (ref "IC7") (pin "1") (pinfunction "OUT_1") (pintype "output"))
      (node (ref "IC7") (pin "2") (pinfunction "-IN_2") (pintype "input"))
      (node (ref "R22") (pin "1") (pinfunction "1_1") (pintype "passive"))
      (node (ref "R23") (pin "1") (pinfunction "1_1") (pintype "passive"))
      (node (ref "R24") (pin "1") (pinfunction "1_1") (pintype "passive"))
      (node (ref "R47") (pin "2") (pinfunction "2_2") (pintype "passive"))
      (node (ref "R53") (pin "1") (pinfunction "1_1") (pintype "passive"))
      (node (ref "R54") (pin "1") (pinfunction "1_1") (pintype "passive"))
    )
    (net (code "8") (name "/FLT_CV") (class "Default")
      (node (ref "C11") (pin "2") (pinfunction "2_2") (pintype "passive"))
      (node (ref "IC8") (pin "10") (pinfunction "+IN_10") (pintype "input"))
      (node (ref "IC9") (pin "5") (pinfunction "X5_5") (pintype "bidirectional"))
    )
    (net (code "9") (name "/N$92") (class "Default")
      (node (ref "IC7") (pin "6") (pinfunction "-IN_6") (pintype "input"))
      (node (ref "IC7") (pin "7") (pinfunction "OUT_7") (pintype "output"))
      (node (ref "R41") (pin "1") (pinfunction "1_1") (pintype "passive"))
    )
    (net (code "10") (name "/NOISE") (class "Default")
      (node (ref "PAD11") (pin "1") (pinfunction "P_1") (pintype "passive"))
      (node (ref "R34") (pin "2") (pinfunction "2_2") (pintype "passive"))
      (node (ref "R37") (pin "2") (pinfunction "2_2") (pintype "passive"))
    )
    (net (code "11") (name "/NOISE_CV") (class "Default")
      (node (ref "C13") (pin "2") (pinfunction "2_2") (pintype "passive"))
      (node (ref "IC10") (pin "12") (pinfunction "+IN_12") (pintype "input"))
      (node (ref "IC9") (pin "15") (pinfunction "X2_15") (pintype "bidirectional"))
    )
    (net (code "12") (name "/OVR-T_CV") (class "Default")
      (node (ref "C14") (pin "2") (pinfunction "2_2") (pintype "passive"))
      (node (ref "IC10") (pin "5") (pinfunction "+IN_5") (pintype "input"))
      (node (ref "IC9") (pin "12") (pinfunction "X3_12") (pintype "bidirectional"))
    )
    (net (code "13") (name "/PITCH_CV") (class "Default")
      (node (ref "C12") (pin "2") (pinfunction "2_2") (pintype "passive"))
      (node (ref "IC10") (pin "10") (pinfunction "+IN_10") (pintype "input"))
      (node (ref "IC9") (pin "13") (pinfunction "X0_13") (pintype "bidirectional"))
    )
    (net (code "14") (name "/TRIG") (class "Default")
      (node (ref "D1") (pin "A") (pinfunction "A_A") (pintype "passive"))
      (node (ref "R67") (pin "1") (pinfunction "1_1") (pintype "passive"))
      (node (ref "T5") (pin "B") (pinfunction "B_B") (pintype "passive"))
      (node (ref "T6") (pin "B") (pinfunction "B_B") (pintype "passive"))
    )
    (net (code "15") (name "/VOL_CV") (class "Default")
      (node (ref "C10") (pin "2") (pinfunction "2_2") (pintype "passive"))
      (node (ref "IC8") (pin "5") (pinfunction "+IN_5") (pintype "input"))
      (node (ref "IC9") (pin "4") (pinfunction "X7_4") (pintype "bidirectional"))
    )
    (net (code "16") (name "GND") (class "Default")
      (node (ref "C10") (pin "1") (pinfunction "1_1") (pintype "passive"))
      (node (ref "C11") (pin "1") (pinfunction "1_1") (pintype "passive"))
      (node (ref "C12") (pin "1") (pinfunction "1_1") (pintype "passive"))
      (node (ref "C13") (pin "1") (pinfunction "1_1") (pintype "passive"))
      (node (ref "C14") (pin "1") (pinfunction "1_1") (pintype "passive"))
      (node (ref "C15") (pin "1") (pinfunction "1_1") (pintype "passive"))
      (node (ref "C16") (pin "2") (pinfunction "2_2") (pintype "passive"))
      (node (ref "C20") (pin "-") (pinfunction "-_-") (pintype "passive"))
      (node (ref "C22") (pin "-") (pinfunction "-_-") (pintype "passive"))
      (node (ref "C25") (pin "1") (pinfunction "1_1") (pintype "passive"))
      (node (ref "C26") (pin "1") (pinfunction "1_1") (pintype "passive"))
      (node (ref "C29") (pin "-") (pinfunction "-_-") (pintype "passive"))
      (node (ref "C5") (pin "1") (pinfunction "1_1") (pintype "passive"))
      (node (ref "C8") (pin "1") (pinfunction "1_1") (pintype "passive"))
      (node (ref "C9") (pin "1") (pinfunction "1_1") (pintype "passive"))
      (node (ref "IC1") (pin "7") (pinfunction "VSS_7") (pintype "power_in"))
      (node (ref "IC13") (pin "7") (pinfunction "VSS_7") (pintype "power_in"))
      (node (ref "IC14") (pin "5") (pinfunction "+IN_5") (pintype "input"))
      (node (ref "IC2") (pin "7") (pinfunction "VSS_7") (pintype "power_in"))
      (node (ref "IC3") (pin "7") (pinfunction "VSS_7") (pintype "power_in"))
      (node (ref "IC3") (pin "9") (pinfunction "I_9") (pintype "input"))
      (node (ref "IC4") (pin "4") (pinfunction "V-_4") (pintype "power_in"))
      (node (ref "IC5") (pin "4") (pinfunction "V-_4") (pintype "power_in"))
      (node (ref "IC6") (pin "3") (pinfunction "+IN_3") (pintype "input"))
      (node (ref "IC6") (pin "5") (pinfunction "+IN_5") (pintype "input"))
      (node (ref "IC9") (pin "8") (pinfunction "GND_8") (pintype "power_in"))
      (node (ref "R100") (pin "1") (pinfunction "1_1") (pintype "passive"))
      (node (ref "R101") (pin "1") (pinfunction "1_1") (pintype "passive"))
      (node (ref "R102") (pin "1") (pinfunction "1_1") (pintype "passive"))
      (node (ref "R103") (pin "1") (pinfunction "1_1") (pintype "passive"))
      (node (ref "R104") (pin "1") (pinfunction "1_1") (pintype "passive"))
      (node (ref "R105") (pin "1") (pinfunction "1_1") (pintype "passive"))
      (node (ref "R106") (pin "1") (pinfunction "1_1") (pintype "passive"))
      (node (ref "R107") (pin "1") (pinfunction "1_1") (pintype "passive"))
      (node (ref "R108") (pin "1") (pinfunction "1_1") (pintype "passive"))
      (node (ref "R109") (pin "1") (pinfunction "1_1") (pintype "passive"))
      (node (ref "R110") (pin "1") (pinfunction "1_1") (pintype "passive"))
      (node (ref "R111") (pin "1") (pinfunction "1_1") (pintype "passive"))
      (node (ref "R112") (pin "1") (pinfunction "1_1") (pintype "passive"))
      (node (ref "R18") (pin "1") (pinfunction "1_1") (pintype "passive"))
      (node (ref "R20") (pin "1") (pinfunction "1_1") (pintype "passive"))
      (node (ref "R27") (pin "1") (pinfunction "1_1") (pintype "passive"))
      (node (ref "R29") (pin "1") (pinfunction "1_1") (pintype "passive"))
      (node (ref "R33") (pin "2") (pinfunction "2_2") (pintype "passive"))
      (node (ref "R40") (pin "2") (pinfunction "2_2") (pintype "passive"))
      (node (ref "R52") (pin "1") (pinfunction "1_1") (pintype "passive"))
      (node (ref "R55") (pin "2") (pinfunction "2_2") (pintype "passive"))
      (node (ref "R69") (pin "1") (pinfunction "1_1") (pintype "passive"))
      (node (ref "R72") (pin "1") (pinfunction "1_1") (pintype "passive"))
      (node (ref "R80") (pin "2") (pinfunction "2_2") (pintype "passive"))
      (node (ref "R81") (pin "2") (pinfunction "2_2") (pintype "passive"))
      (node (ref "R83") (pin "1") (pinfunction "1_1") (pintype "passive"))
      (node (ref "R84") (pin "1") (pinfunction "1_1") (pintype "passive"))
      (node (ref "R89") (pin "1") (pinfunction "1_1") (pintype "passive"))
      (node (ref "R90") (pin "1") (pinfunction "1_1") (pintype "passive"))
      (node (ref "R91") (pin "1") (pinfunction "1_1") (pintype "passive"))
      (node (ref "R92") (pin "1") (pinfunction "1_1") (pintype "passive"))
      (node (ref "R93") (pin "1") (pinfunction "1_1") (pintype "passive"))
      (node (ref "R94") (pin "1") (pinfunction "1_1") (pintype "passive"))
      (node (ref "R95") (pin "1") (pinfunction "1_1") (pintype "passive"))
      (node (ref "R96") (pin "1") (pinfunction "1_1") (pintype "passive"))
      (node (ref "R97") (pin "1") (pinfunction "1_1") (pintype "passive"))
      (node (ref "R98") (pin "1") (pinfunction "1_1") (pintype "passive"))
      (node (ref "R99") (pin "1") (pinfunction "1_1") (pintype "passive"))
    )
    (net (code "17") (name "Net-(C4-Pad-)") (class "Default")
      (node (ref "C4") (pin "-") (pinfunction "-_-") (pintype "passive"))
      (node (ref "R12") (pin "1") (pinfunction "1_1") (pintype "passive"))
    )
    (net (code "18") (name "Net-(C5-Pad2)") (class "Default")
      (node (ref "C5") (pin "2") (pinfunction "2_2") (pintype "passive"))
      (node (ref "R12") (pin "2") (pinfunction "2_2") (pintype "passive"))
      (node (ref "R13") (pin "1") (pinfunction "1_1") (pintype "passive"))
    )
    (net (code "19") (name "Net-(C7-Pad+)") (class "Default")
      (node (ref "C7") (pin "+") (pinfunction "+_+") (pintype "passive"))
      (node (ref "R15") (pin "2") (pinfunction "2_2") (pintype "passive"))
    )
    (net (code "20") (name "Net-(C17-Pad2)") (class "Default")
      (node (ref "C17") (pin "2") (pinfunction "2_2") (pintype "passive"))
      (node (ref "R93") (pin "2") (pinfunction "2_2") (pintype "passive"))
    )
    (net (code "21") (name "Net-(C18-Pad1)") (class "Default")
      (node (ref "C18") (pin "1") (pinfunction "1_1") (pintype "passive"))
      (node (ref "R98") (pin "2") (pinfunction "2_2") (pintype "passive"))
    )
    (net (code "22") (name "Net-(C19-Pad-)") (class "Default")
      (node (ref "C19") (pin "-") (pinfunction "-_-") (pintype "passive"))
      (node (ref "R51") (pin "2") (pinfunction "2_2") (pintype "passive"))
      (node (ref "R52") (pin "2") (pinfunction "2_2") (pintype "passive"))
    )
    (net (code "23") (name "Net-(C27-Pad-)") (class "Default")
      (node (ref "C27") (pin "-") (pinfunction "-_-") (pintype "passive"))
      (node (ref "R63") (pin "1") (pinfunction "1_1") (pintype "passive"))
      (node (ref "R64") (pin "1") (pinfunction "1_1") (pintype "passive"))
    )
    (net (code "24") (name "Net-(C28-Pad2)") (class "Default")
      (node (ref "C28") (pin "2") (pinfunction "2_2") (pintype "passive"))
      (node (ref "R100") (pin "2") (pinfunction "2_2") (pintype "passive"))
    )
    (net (code "25") (name "Net-(IC1A-I)") (class "Default")
      (node (ref "C1") (pin "1") (pinfunction "1_1") (pintype "passive"))
      (node (ref "IC1") (pin "1") (pinfunction "I_1") (pintype "input"))
      (node (ref "IC2") (pin "1") (pinfunction "A_1") (pintype "tri_state"))
    )
    (net (code "26") (name "Net-(IC1A-O)") (class "Default")
      (node (ref "C1") (pin "2") (pinfunction "2_2") (pintype "passive"))
      (node (ref "IC1") (pin "2") (pinfunction "O_2") (pintype "output"))
      (node (ref "R15") (pin "1") (pinfunction "1_1") (pintype "passive"))
      (node (ref "R3") (pin "1") (pinfunction "1_1") (pintype "passive"))
    )
    (net (code "27") (name "Net-(IC1B-I)") (class "Default")
      (node (ref "IC1") (pin "3") (pinfunction "I_3") (pintype "input"))
      (node (ref "R1") (pin "2") (pinfunction "2_2") (pintype "passive"))
      (node (ref "R3") (pin "2") (pinfunction "2_2") (pintype "passive"))
      (node (ref "R4") (pin "1") (pinfunction "1_1") (pintype "passive"))
    )
    (net (code "28") (name "Net-(IC1B-O)") (class "Default")
      (node (ref "IC1") (pin "4") (pinfunction "O_4") (pintype "output"))
      (node (ref "IC1") (pin "5") (pinfunction "I_5") (pintype "input"))
    )
    (net (code "29") (name "Net-(IC1C-O)") (class "Default")
      (node (ref "IC1") (pin "6") (pinfunction "O_6") (pintype "output"))
      (node (ref "R1") (pin "1") (pinfunction "1_1") (pintype "passive"))
      (node (ref "R5") (pin "2") (pinfunction "2_2") (pintype "passive"))
    )
    (net (code "30") (name "Net-(IC1D-I)") (class "Default")
      (node (ref "IC1") (pin "10") (pinfunction "O_10") (pintype "output"))
      (node (ref "IC1") (pin "9") (pinfunction "I_9") (pintype "input"))
    )
    (net (code "31") (name "Net-(IC1D-O)") (class "Default")
      (node (ref "IC1") (pin "8") (pinfunction "O_8") (pintype "output"))
      (node (ref "R2") (pin "2") (pinfunction "2_2") (pintype "passive"))
      (node (ref "R7") (pin "2") (pinfunction "2_2") (pintype "passive"))
    )
    (net (code "32") (name "Net-(IC1E-I)") (class "Default")
      (node (ref "IC1") (pin "11") (pinfunction "I_11") (pintype "input"))
      (node (ref "R2") (pin "1") (pinfunction "1_1") (pintype "passive"))
      (node (ref "R6") (pin "2") (pinfunction "2_2") (pintype "passive"))
    )
    (net (code "33") (name "Net-(IC1F-I)") (class "Default")
      (node (ref "C2") (pin "1") (pinfunction "1_1") (pintype "passive"))
      (node (ref "IC1") (pin "13") (pinfunction "I_13") (pintype "input"))
      (node (ref "IC2") (pin "3") (pinfunction "B_3") (pintype "tri_state"))
    )
    (net (code "34") (name "Net-(IC1F-O)") (class "Default")
      (node (ref "C2") (pin "2") (pinfunction "2_2") (pintype "passive"))
      (node (ref "IC1") (pin "12") (pinfunction "O_12") (pintype "output"))
      (node (ref "R4") (pin "2") (pinfunction "2_2") (pintype "passive"))
      (node (ref "R6") (pin "1") (pinfunction "1_1") (pintype "passive"))
    )
    (net (code "35") (name "Net-(IC2A-B)") (class "Default")
      (node (ref "IC2") (pin "2") (pinfunction "B_2") (pintype "tri_state"))
      (node (ref "R5") (pin "1") (pinfunction "1_1") (pintype "passive"))
    )
    (net (code "36") (name "Net-(IC2C-A)") (class "Default")
      (node (ref "IC2") (pin "4") (pinfunction "A_4") (pintype "tri_state"))
      (node (ref "R7") (pin "1") (pinfunction "1_1") (pintype "passive"))
    )
    (net (code "37") (name "Net-(IC2D-A)") (class "Default")
      (node (ref "IC2") (pin "8") (pinfunction "A_8") (pintype "tri_state"))
      (node (ref "IC3") (pin "6") (pinfunction "O_6") (pintype "output"))
      (node (ref "R10") (pin "2") (pinfunction "2_2") (pintype "passive"))
    )
    (net (code "38") (name "Net-(IC2D-B)") (class "Default")
      (node (ref "IC2") (pin "9") (pinfunction "B_9") (pintype "tri_state"))
      (node (ref "R8") (pin "2") (pinfunction "2_2") (pintype "passive"))
    )
    (net (code "39") (name "Net-(IC3A-I)") (class "Default")
      (node (ref "C3") (pin "1") (pinfunction "1_1") (pintype "passive"))
      (node (ref "IC3") (pin "1") (pinfunction "I_1") (pintype "input"))
      (node (ref "R8") (pin "1") (pinfunction "1_1") (pintype "passive"))
    )
    (net (code "40") (name "Net-(IC3A-O)") (class "Default")
      (node (ref "C3") (pin "2") (pinfunction "2_2") (pintype "passive"))
      (node (ref "C4") (pin "+") (pinfunction "+_+") (pintype "passive"))
      (node (ref "IC3") (pin "2") (pinfunction "O_2") (pintype "output"))
      (node (ref "R9") (pin "1") (pinfunction "1_1") (pintype "passive"))
    )
    (net (code "41") (name "Net-(IC3B-I)") (class "Default")
      (node (ref "IC3") (pin "3") (pinfunction "I_3") (pintype "input"))
      (node (ref "R10") (pin "1") (pinfunction "1_1") (pintype "passive"))
      (node (ref "R9") (pin "2") (pinfunction "2_2") (pintype "passive"))
    )
    (net (code "42") (name "Net-(IC3B-O)") (class "Default")
      (node (ref "IC3") (pin "4") (pinfunction "O_4") (pintype "output"))
      (node (ref "IC3") (pin "5") (pinfunction "I_5") (pintype "input"))
    )
    (net (code "43") (name "Net-(IC3E-I)") (class "Default")
      (node (ref "IC3") (pin "11") (pinfunction "I_11") (pintype "input"))
      (node (ref "IC3") (pin "12") (pinfunction "O_12") (pintype "output"))
    )
    (net (code "44") (name "Net-(IC4A-+IN)") (class "Default")
      (node (ref "IC4") (pin "3") (pinfunction "+IN_3") (pintype "input"))
      (node (ref "R14") (pin "2") (pinfunction "2_2") (pintype "passive"))
      (node (ref "R16") (pin "1") (pinfunction "1_1") (pintype "passive"))
      (node (ref "R18") (pin "2") (pinfunction "2_2") (pintype "passive"))
    )
    (net (code "45") (name "Net-(IC4A--IN)") (class "Default")
      (node (ref "IC4") (pin "2") (pinfunction "-IN_2") (pintype "input"))
      (node (ref "Q1") (pin "4") (pinfunction "C2_4") (pintype "passive"))
      (node (ref "R19") (pin "2") (pinfunction "2_2") (pintype "passive"))
    )
    (net (code "46") (name "Net-(IC4B-+IN)") (class "Default")
      (node (ref "IC4") (pin "5") (pinfunction "+IN_5") (pintype "input"))
      (node (ref "R11") (pin "2") (pinfunction "2_2") (pintype "passive"))
      (node (ref "R20") (pin "2") (pinfunction "2_2") (pintype "passive"))
      (node (ref "R21") (pin "1") (pinfunction "1_1") (pintype "passive"))
      (node (ref "R22") (pin "2") (pinfunction "2_2") (pintype "passive"))
    )
    (net (code "47") (name "Net-(IC4B--IN)") (class "Default")
      (node (ref "IC4") (pin "6") (pinfunction "-IN_6") (pintype "input"))
      (node (ref "PAD1") (pin "1") (pinfunction "P_1") (pintype "passive"))
      (node (ref "R19") (pin "1") (pinfunction "1_1") (pintype "passive"))
    )
    (net (code "48") (name "Net-(IC5A-+IN)") (class "Default")
      (node (ref "C26") (pin "2") (pinfunction "2_2") (pintype "passive"))
      (node (ref "IC5") (pin "3") (pinfunction "+IN_3") (pintype "input"))
      (node (ref "R68") (pin "1") (pinfunction "1_1") (pintype "passive"))
    )
    (net (code "49") (name "Net-(IC5A--IN)") (class "Default")
      (node (ref "IC5") (pin "2") (pinfunction "-IN_2") (pintype "input"))
      (node (ref "R69") (pin "2") (pinfunction "2_2") (pintype "passive"))
      (node (ref "R70") (pin "1") (pinfunction "1_1") (pintype "passive"))
    )
    (net (code "50") (name "Net-(IC5A-OUT)") (class "Default")
      (node (ref "D1") (pin "C") (pinfunction "C_C") (pintype "passive"))
      (node (ref "IC5") (pin "1") (pinfunction "OUT_1") (pintype "output"))
      (node (ref "R66") (pin "2") (pinfunction "2_2") (pintype "passive"))
    )
    (net (code "51") (name "Net-(IC5B-+IN)") (class "Default")
      (node (ref "C30") (pin "2") (pinfunction "2_2") (pintype "passive"))
      (node (ref "IC5") (pin "5") (pinfunction "+IN_5") (pintype "input"))
      (node (ref "R84") (pin "2") (pinfunction "2_2") (pintype "passive"))
    )
    (net (code "52") (name "Net-(IC5B--IN)") (class "Default")
      (node (ref "IC5") (pin "6") (pinfunction "-IN_6") (pintype "input"))
      (node (ref "R83") (pin "2") (pinfunction "2_2") (pintype "passive"))
      (node (ref "T7") (pin "E") (pinfunction "E_E") (pintype "passive"))
    )
    (net (code "53") (name "Net-(IC5B-OUT)") (class "Default")
      (node (ref "IC5") (pin "7") (pinfunction "OUT_7") (pintype "output"))
      (node (ref "R65") (pin "2") (pinfunction "2_2") (pintype "passive"))
      (node (ref "R68") (pin "2") (pinfunction "2_2") (pintype "passive"))
    )
    (net (code "54") (name "Net-(IC6A--IN)") (class "Default")
      (node (ref "C17") (pin "1") (pinfunction "1_1") (pintype "passive"))
      (node (ref "IC6") (pin "2") (pinfunction "-IN_2") (pintype "input"))
      (node (ref "Q1") (pin "2") (pinfunction "C1_2") (pintype "passive"))
      (node (ref "R23") (pin "2") (pinfunction "2_2") (pintype "passive"))
      (node (ref "R51") (pin "1") (pinfunction "1_1") (pintype "passive"))
    )
    (net (code "55") (name "Net-(IC6A-OUT)") (class "Default")
      (node (ref "IC6") (pin "1") (pinfunction "OUT_1") (pintype "output"))
      (node (ref "Q1") (pin "3") (pinfunction "E_3") (pintype "passive"))
    )
    (net (code "56") (name "Net-(IC6B--IN)") (class "Default")
      (node (ref "C18") (pin "2") (pinfunction "2_2") (pintype "passive"))
      (node (ref "IC6") (pin "6") (pinfunction "-IN_6") (pintype "input"))
      (node (ref "Q2") (pin "4") (pinfunction "C2_4") (pintype "passive"))
      (node (ref "R47") (pin "1") (pinfunction "1_1") (pintype "passive"))
    )
    (net (code "57") (name "Net-(IC6B-OUT)") (class "Default")
      (node (ref "IC6") (pin "7") (pinfunction "OUT_7") (pintype "output"))
      (node (ref "Q2") (pin "3") (pinfunction "E_3") (pintype "passive"))
    )
    (net (code "58") (name "Net-(IC7A-+IN)") (class "Default")
      (node (ref "C20") (pin "+") (pinfunction "+_+") (pintype "passive"))
      (node (ref "IC7") (pin "3") (pinfunction "+IN_3") (pintype "input"))
      (node (ref "Q2") (pin "2") (pinfunction "C1_2") (pintype "passive"))
      (node (ref "T5") (pin "E") (pinfunction "E_E") (pintype "passive"))
    )
    (net (code "59") (name "Net-(IC7B-+IN)") (class "Default")
      (node (ref "C22") (pin "+") (pinfunction "+_+") (pintype "passive"))
      (node (ref "IC7") (pin "5") (pinfunction "+IN_5") (pintype "input"))
      (node (ref "R55") (pin "1") (pinfunction "1_1") (pintype "passive"))
      (node (ref "T6") (pin "E") (pinfunction "E_E") (pintype "passive"))
    )
    (net (code "60") (name "Net-(IC8A--IN)") (class "Default")
      (node (ref "IC8") (pin "1") (pinfunction "OUT_1") (pintype "output"))
      (node (ref "IC8") (pin "2") (pinfunction "-IN_2") (pintype "input"))
      (node (ref "R46") (pin "1") (pinfunction "1_1") (pintype "passive"))
    )
    (net (code "61") (name "Net-(IC8B--IN)") (class "Default")
      (node (ref "IC8") (pin "6") (pinfunction "-IN_6") (pintype "input"))
      (node (ref "IC8") (pin "7") (pinfunction "OUT_7") (pintype "output"))
      (node (ref "R57") (pin "1") (pinfunction "1_1") (pintype "passive"))
    )
    (net (code "62") (name "Net-(IC8C--IN)") (class "Default")
      (node (ref "IC8") (pin "8") (pinfunction "OUT_8") (pintype "output"))
      (node (ref "IC8") (pin "9") (pinfunction "-IN_9") (pintype "input"))
      (node (ref "R11") (pin "1") (pinfunction "1_1") (pintype "passive"))
    )
    (net (code "63") (name "Net-(IC8D--IN)") (class "Default")
      (node (ref "IC8") (pin "13") (pinfunction "-IN_13") (pintype "input"))
      (node (ref "IC8") (pin "14") (pinfunction "OUT_14") (pintype "output"))
      (node (ref "R42") (pin "2") (pinfunction "2_2") (pintype "passive"))
    )
    (net (code "64") (name "Net-(IC9A-A)") (class "Default")
      (node (ref "IC9") (pin "11") (pinfunction "A_11") (pintype "input"))
      (node (ref "PAD3") (pin "1") (pinfunction "P_1") (pintype "passive"))
    )
    (net (code "65") (name "Net-(IC9A-B)") (class "Default")
      (node (ref "IC9") (pin "10") (pinfunction "B_10") (pintype "input"))
      (node (ref "PAD4") (pin "1") (pinfunction "P_1") (pintype "passive"))
    )
    (net (code "66") (name "Net-(IC9A-C)") (class "Default")
      (node (ref "IC9") (pin "9") (pinfunction "C_9") (pintype "input"))
      (node (ref "PAD5") (pin "1") (pinfunction "P_1") (pintype "passive"))
    )
    (net (code "67") (name "Net-(IC9A-INH)") (class "Default")
      (node (ref "IC9") (pin "6") (pinfunction "INH_6") (pintype "input"))
      (node (ref "PAD2") (pin "1") (pinfunction "P_1") (pintype "passive"))
      (node (ref "R25") (pin "1") (pinfunction "1_1") (pintype "passive"))
    )
    (net (code "68") (name "Net-(IC9A-X)") (class "Default")
      (node (ref "IC9") (pin "3") (pinfunction "X_3") (pintype "bidirectional"))
      (node (ref "PAD6") (pin "1") (pinfunction "P_1") (pintype "passive"))
    )
    (net (code "69") (name "Net-(IC10A--IN)") (class "Default")
      (node (ref "IC10") (pin "1") (pinfunction "OUT_1") (pintype "output"))
      (node (ref "IC10") (pin "2") (pinfunction "-IN_2") (pintype "input"))
      (node (ref "R43") (pin "2") (pinfunction "2_2") (pintype "passive"))
    )
    (net (code "70") (name "Net-(IC10B--IN)") (class "Default")
      (node (ref "IC10") (pin "6") (pinfunction "-IN_6") (pintype "input"))
      (node (ref "IC10") (pin "7") (pinfunction "OUT_7") (pintype "output"))
      (node (ref "R28") (pin "2") (pinfunction "2_2") (pintype "passive"))
    )
    (net (code "71") (name "Net-(IC10C--IN)") (class "Default")
      (node (ref "IC10") (pin "8") (pinfunction "OUT_8") (pintype "output"))
      (node (ref "IC10") (pin "9") (pinfunction "-IN_9") (pintype "input"))
      (node (ref "R14") (pin "1") (pinfunction "1_1") (pintype "passive"))
    )
    (net (code "72") (name "Net-(IC10D--IN)") (class "Default")
      (node (ref "IC10") (pin "13") (pinfunction "-IN_13") (pintype "input"))
      (node (ref "IC10") (pin "14") (pinfunction "OUT_14") (pintype "output"))
      (node (ref "R26") (pin "2") (pinfunction "2_2") (pintype "passive"))
    )
    (net (code "73") (name "Net-(IC11A-+IN)") (class "Default")
      (node (ref "C7") (pin "-") (pinfunction "-_-") (pintype "passive"))
      (node (ref "IC11") (pin "3") (pinfunction "+IN_3") (pintype "input"))
      (node (ref "R112") (pin "2") (pinfunction "2_2") (pintype "passive"))
    )
    (net (code "74") (name "Net-(IC11A--IN)") (class "Default")
      (node (ref "IC11") (pin "4") (pinfunction "-IN_4") (pintype "input"))
      (node (ref "R27") (pin "2") (pinfunction "2_2") (pintype "passive"))
    )
    (net (code "75") (name "Net-(IC11A-AMP{slash}BIAS)") (class "Default")
      (node (ref "IC11") (pin "1") (pinfunction "AMP/BIAS_1") (pintype "passive"))
      (node (ref "T1") (pin "4") (pinfunction "C2_4") (pintype "passive"))
    )
    (net (code "76") (name "Net-(IC11A-OUT)") (class "Default")
      (node (ref "IC11") (pin "14") (pinfunction "+IN_14") (pintype "input"))
      (node (ref "IC11") (pin "5") (pinfunction "OUT_5") (pintype "output"))
      (node (ref "R106") (pin "2") (pinfunction "2_2") (pintype "passive"))
      (node (ref "R13") (pin "2") (pinfunction "2_2") (pintype "passive"))
    )
    (net (code "77") (name "Net-(IC11B--IN)") (class "Default")
      (node (ref "IC11") (pin "13") (pinfunction "-IN_13") (pintype "input"))
      (node (ref "R107") (pin "2") (pinfunction "2_2") (pintype "passive"))
    )
    (net (code "78") (name "Net-(IC11B-AMP{slash}BIAS)") (class "Default")
      (node (ref "IC11") (pin "16") (pinfunction "AMP/BIAS_16") (pintype "passive"))
      (node (ref "T2") (pin "2") (pinfunction "C1_2") (pintype "passive"))
    )
    (net (code "79") (name "Net-(IC11B-OUT)") (class "Default")
      (node (ref "C16") (pin "1") (pinfunction "1_1") (pintype "passive"))
      (node (ref "IC11") (pin "12") (pinfunction "OUT_12") (pintype "output"))
      (node (ref "IC12") (pin "5") (pinfunction "OUT_5") (pintype "output"))
      (node (ref "IC12") (pin "7") (pinfunction "BUFF/IN_7") (pintype "input"))
      (node (ref "R33") (pin "1") (pinfunction "1_1") (pintype "passive"))
    )
    (net (code "80") (name "Net-(IC12A-+IN)") (class "Default")
      (node (ref "IC12") (pin "3") (pinfunction "+IN_3") (pintype "input"))
      (node (ref "R110") (pin "2") (pinfunction "2_2") (pintype "passive"))
      (node (ref "R34") (pin "1") (pinfunction "1_1") (pintype "passive"))
    )
    (net (code "81") (name "Net-(IC12A--IN)") (class "Default")
      (node (ref "IC12") (pin "4") (pinfunction "-IN_4") (pintype "input"))
      (node (ref "R111") (pin "2") (pinfunction "2_2") (pintype "passive"))
    )
    (net (code "82") (name "Net-(IC12A-AMP{slash}BIAS)") (class "Default")
      (node (ref "IC12") (pin "1") (pinfunction "AMP/BIAS_1") (pintype "passive"))
      (node (ref "T3") (pin "2") (pinfunction "C1_2") (pintype "passive"))
    )
    (net (code "83") (name "Net-(IC12A-BUFF{slash}OUT)") (class "Default")
      (node (ref "IC12") (pin "8") (pinfunction "BUFF/OUT_8") (pintype "output"))
      (node (ref "R44") (pin "2") (pinfunction "2_2") (pintype "passive"))
      (node (ref "R64") (pin "2") (pinfunction "2_2") (pintype "passive"))
    )
    (net (code "84") (name "Net-(IC12B-+IN)") (class "Default")
      (node (ref "IC12") (pin "14") (pinfunction "+IN_14") (pintype "input"))
      (node (ref "R101") (pin "2") (pinfunction "2_2") (pintype "passive"))
      (node (ref "R37") (pin "1") (pinfunction "1_1") (pintype "passive"))
    )
    (net (code "85") (name "Net-(IC12B--IN)") (class "Default")
      (node (ref "IC12") (pin "13") (pinfunction "-IN_13") (pintype "input"))
      (node (ref "R102") (pin "2") (pinfunction "2_2") (pintype "passive"))
    )
    (net (code "86") (name "Net-(IC12B-AMP{slash}BIAS)") (class "Default")
      (node (ref "IC12") (pin "16") (pinfunction "AMP/BIAS_16") (pintype "passive"))
      (node (ref "T4") (pin "2") (pinfunction "C1_2") (pintype "passive"))
    )
    (net (code "87") (name "Net-(IC12B-BUFF{slash}IN)") (class "Default")
      (node (ref "IC12") (pin "10") (pinfunction "BUFF/IN_10") (pintype "input"))
      (node (ref "IC12") (pin "12") (pinfunction "OUT_12") (pintype "output"))
      (node (ref "R40") (pin "1") (pinfunction "1_1") (pintype "passive"))
    )
    (net (code "88") (name "Net-(IC12B-BUFF{slash}OUT)") (class "Default")
      (node (ref "C21") (pin "1") (pinfunction "1_1") (pintype "passive"))
      (node (ref "IC12") (pin "9") (pinfunction "BUFF/OUT_9") (pintype "output"))
      (node (ref "R45") (pin "2") (pinfunction "2_2") (pintype "passive"))
    )
    (net (code "89") (name "Net-(IC13A-A)") (class "Default")
      (node (ref "IC13") (pin "1") (pinfunction "A_1") (pintype "tri_state"))
      (node (ref "R59") (pin "1") (pinfunction "1_1") (pintype "passive"))
    )
    (net (code "90") (name "Net-(IC13A-B)") (class "Default")
      (node (ref "C24") (pin "1") (pinfunction "1_1") (pintype "passive"))
      (node (ref "IC13") (pin "2") (pinfunction "B_2") (pintype "tri_state"))
      (node (ref "IC13") (pin "3") (pinfunction "B_3") (pintype "tri_state"))
    )
    (net (code "91") (name "Net-(IC13B-A)") (class "Default")
      (node (ref "C21") (pin "2") (pinfunction "2_2") (pintype "passive"))
      (node (ref "C23") (pin "2") (pinfunction "2_2") (pintype "passive"))
      (node (ref "IC13") (pin "11") (pinfunction "A_11") (pintype "tri_state"))
    )
    (net (code "92") (name "Net-(IC13C-A)") (class "Default")
      (node (ref "IC13") (pin "4") (pinfunction "A_4") (pintype "tri_state"))
      (node (ref "R58") (pin "1") (pinfunction "1_1") (pintype "passive"))
    )
    (net (code "93") (name "Net-(IC13D-A)") (class "Default")
      (node (ref "IC13") (pin "8") (pinfunction "A_8") (pintype "tri_state"))
      (node (ref "IC15") (pin "5") (pinfunction "+IN_5") (pintype "input"))
      (node (ref "PAD7") (pin "1") (pinfunction "P_1") (pintype "passive"))
      (node (ref "R77") (pin "2") (pinfunction "2_2") (pintype "passive"))
    )
    (net (code "94") (name "Net-(IC13D-B)") (class "Default")
      (node (ref "IC13") (pin "9") (pinfunction "B_9") (pintype "tri_state"))
      (node (ref "R56") (pin "2") (pinfunction "2_2") (pintype "passive"))
    )
    (net (code "95") (name "Net-(IC14A-+IN)") (class "Default")
      (node (ref "C25") (pin "2") (pinfunction "2_2") (pintype "passive"))
      (node (ref "IC14") (pin "3") (pinfunction "+IN_3") (pintype "input"))
      (node (ref "R59") (pin "2") (pinfunction "2_2") (pintype "passive"))
    )
    (net (code "96") (name "Net-(IC14A--IN)") (class "Default")
      (node (ref "C24") (pin "2") (pinfunction "2_2") (pintype "passive"))
      (node (ref "IC14") (pin "1") (pinfunction "OUT_1") (pintype "output"))
      (node (ref "IC14") (pin "2") (pinfunction "-IN_2") (pintype "input"))
      (node (ref "R61") (pin "1") (pinfunction "1_1") (pintype "passive"))
    )
    (net (code "97") (name "Net-(IC14B--IN)") (class "Default")
      (node (ref "C28") (pin "1") (pinfunction "1_1") (pintype "passive"))
      (node (ref "IC14") (pin "6") (pinfunction "-IN_6") (pintype "input"))
      (node (ref "Q3") (pin "2") (pinfunction "C1_2") (pintype "passive"))
      (node (ref "R53") (pin "2") (pinfunction "2_2") (pintype "passive"))
    )
    (net (code "98") (name "Net-(IC14B-OUT)") (class "Default")
      (node (ref "IC14") (pin "7") (pinfunction "OUT_7") (pintype "output"))
      (node (ref "Q3") (pin "3") (pinfunction "E_3") (pintype "passive"))
    )
    (net (code "99") (name "Net-(IC15A-+IN)") (class "Default")
      (node (ref "C23") (pin "1") (pinfunction "1_1") (pintype "passive"))
      (node (ref "IC15") (pin "3") (pinfunction "+IN_3") (pintype "input"))
      (node (ref "R56") (pin "1") (pinfunction "1_1") (pintype "passive"))
    )
    (net (code "100") (name "Net-(IC15A--IN)") (class "Default")
      (node (ref "IC15") (pin "1") (pinfunction "OUT_1") (pintype "output"))
      (node (ref "IC15") (pin "2") (pinfunction "-IN_2") (pintype "input"))
      (node (ref "R60") (pin "1") (pinfunction "1_1") (pintype "passive"))
      (node (ref "R63") (pin "2") (pinfunction "2_2") (pintype "passive"))
    )
    (net (code "101") (name "Net-(IC15B--IN)") (class "Default")
      (node (ref "C27") (pin "+") (pinfunction "+_+") (pintype "passive"))
      (node (ref "IC15") (pin "6") (pinfunction "-IN_6") (pintype "input"))
      (node (ref "R62") (pin "2") (pinfunction "2_2") (pintype "passive"))
    )
    (net (code "102") (name "Net-(IC15B-OUT)") (class "Default")
      (node (ref "IC15") (pin "7") (pinfunction "OUT_7") (pintype "output"))
      (node (ref "R58") (pin "2") (pinfunction "2_2") (pintype "passive"))
      (node (ref "R62") (pin "1") (pinfunction "1_1") (pintype "passive"))
    )
    (net (code "103") (name "Net-(IC16A-+IN)") (class "Default")
      (node (ref "C29") (pin "+") (pinfunction "+_+") (pintype "passive"))
      (node (ref "IC16") (pin "3") (pinfunction "+IN_3") (pintype "input"))
      (node (ref "Q6") (pin "3") (pinfunction "E_3") (pintype "passive"))
      (node (ref "R81") (pin "1") (pinfunction "1_1") (pintype "passive"))
    )
    (net (code "104") (name "Net-(IC16A--IN)") (class "Default")
      (node (ref "C30") (pin "1") (pinfunction "1_1") (pintype "passive"))
      (node (ref "IC16") (pin "1") (pinfunction "OUT_1") (pintype "output"))
      (node (ref "IC16") (pin "2") (pinfunction "-IN_2") (pintype "input"))
      (node (ref "R67") (pin "2") (pinfunction "2_2") (pintype "passive"))
      (node (ref "R71") (pin "2") (pinfunction "2_2") (pintype "passive"))
    )
    (net (code "105") (name "Net-(IC16B-+IN)") (class "Default")
      (node (ref "IC16") (pin "5") (pinfunction "+IN_5") (pintype "input"))
      (node (ref "PAD8") (pin "1") (pinfunction "P_1") (pintype "passive"))
      (node (ref "R90") (pin "2") (pinfunction "2_2") (pintype "passive"))
    )
    (net (code "106") (name "Net-(IC16B--IN)") (class "Default")
      (node (ref "IC16") (pin "6") (pinfunction "-IN_6") (pintype "input"))
      (node (ref "R88") (pin "1") (pinfunction "1_1") (pintype "passive"))
      (node (ref "R89") (pin "2") (pinfunction "2_2") (pintype "passive"))
    )
    (net (code "107") (name "Net-(IC16B-OUT)") (class "Default")
      (node (ref "C32") (pin "-") (pinfunction "-_-") (pintype "passive"))
      (node (ref "IC16") (pin "7") (pinfunction "OUT_7") (pintype "output"))
      (node (ref "R88") (pin "2") (pinfunction "2_2") (pintype "passive"))
    )
    (net (code "108") (name "Net-(IC17A-+IN)") (class "Default")
      (node (ref "IC17") (pin "3") (pinfunction "+IN_3") (pintype "input"))
      (node (ref "Q4") (pin "4") (pinfunction "C2_4") (pintype "passive"))
      (node (ref "R76") (pin "1") (pinfunction "1_1") (pintype "passive"))
      (node (ref "R85") (pin "2") (pinfunction "2_2") (pintype "passive"))
    )
    (net (code "109") (name "Net-(IC17A--IN)") (class "Default")
      (node (ref "IC17") (pin "2") (pinfunction "-IN_2") (pintype "input"))
      (node (ref "Q4") (pin "2") (pinfunction "C1_2") (pintype "passive"))
      (node (ref "R75") (pin "1") (pinfunction "1_1") (pintype "passive"))
      (node (ref "R78") (pin "1") (pinfunction "1_1") (pintype "passive"))
    )
    (net (code "110") (name "Net-(IC17A-OUT)") (class "Default")
      (node (ref "IC17") (pin "1") (pinfunction "OUT_1") (pintype "output"))
      (node (ref "IC17") (pin "5") (pinfunction "+IN_5") (pintype "input"))
      (node (ref "R78") (pin "2") (pinfunction "2_2") (pintype "passive"))
    )
    (net (code "111") (name "Net-(IC17B--IN)") (class "Default")
      (node (ref "C31") (pin "2") (pinfunction "2_2") (pintype "passive"))
      (node (ref "IC17") (pin "6") (pinfunction "-IN_6") (pintype "input"))
      (node (ref "R86") (pin "1") (pinfunction "1_1") (pintype "passive"))
      (node (ref "R87") (pin "2") (pinfunction "2_2") (pintype "passive"))
    )
    (net (code "112") (name "Net-(IC17B-OUT)") (class "Default")
      (node (ref "C31") (pin "1") (pinfunction "1_1") (pintype "passive"))
      (node (ref "IC17") (pin "7") (pinfunction "OUT_7") (pintype "output"))
      (node (ref "PAD10") (pin "1") (pinfunction "P_1") (pintype "passive"))
      (node (ref "R86") (pin "2") (pinfunction "2_2") (pintype "passive"))
    )
    (net (code "113") (name "Net-(PAD9-P)") (class "Default")
      (node (ref "PAD9") (pin "1") (pinfunction "P_1") (pintype "passive"))
      (node (ref "R85") (pin "1") (pinfunction "1_1") (pintype "passive"))
      (node (ref "R87") (pin "1") (pinfunction "1_1") (pintype "passive"))
    )
    (net (code "114") (name "Net-(Q1-B1)") (class "Default")
      (node (ref "Q1") (pin "1") (pinfunction "B1_1") (pintype "passive"))
      (node (ref "R48") (pin "1") (pinfunction "1_1") (pintype "passive"))
      (node (ref "R94") (pin "2") (pinfunction "2_2") (pintype "passive"))
    )
    (net (code "115") (name "Net-(Q1-B2)") (class "Default")
      (node (ref "Q1") (pin "5") (pinfunction "B2_5") (pintype "passive"))
      (node (ref "R43") (pin "1") (pinfunction "1_1") (pintype "passive"))
      (node (ref "R92") (pin "2") (pinfunction "2_2") (pintype "passive"))
    )
    (net (code "116") (name "Net-(Q2-B1)") (class "Default")
      (node (ref "Q2") (pin "1") (pinfunction "B1_1") (pintype "passive"))
      (node (ref "R49") (pin "2") (pinfunction "2_2") (pintype "passive"))
      (node (ref "R99") (pin "2") (pinfunction "2_2") (pintype "passive"))
    )
    (net (code "117") (name "Net-(Q2-B2)") (class "Default")
      (node (ref "Q2") (pin "5") (pinfunction "B2_5") (pintype "passive"))
      (node (ref "R46") (pin "2") (pinfunction "2_2") (pintype "passive"))
      (node (ref "R97") (pin "2") (pinfunction "2_2") (pintype "passive"))
    )
    (net (code "118") (name "Net-(Q3-B1)") (class "Default")
      (node (ref "Q3") (pin "1") (pinfunction "B1_1") (pintype "passive"))
      (node (ref "R73") (pin "1") (pinfunction "1_1") (pintype "passive"))
      (node (ref "R91") (pin "2") (pinfunction "2_2") (pintype "passive"))
    )
    (net (code "119") (name "Net-(Q3-B2)") (class "Default")
      (node (ref "Q3") (pin "5") (pinfunction "B2_5") (pintype "passive"))
      (node (ref "R57") (pin "2") (pinfunction "2_2") (pintype "passive"))
      (node (ref "R96") (pin "2") (pinfunction "2_2") (pintype "passive"))
    )
    (net (code "120") (name "Net-(Q3-C2)") (class "Default")
      (node (ref "Q3") (pin "4") (pinfunction "C2_4") (pintype "passive"))
      (node (ref "Q4") (pin "3") (pinfunction "E_3") (pintype "passive"))
    )
    (net (code "121") (name "Net-(Q4-B1)") (class "Default")
      (node (ref "Q4") (pin "1") (pinfunction "B1_1") (pintype "passive"))
      (node (ref "R61") (pin "2") (pinfunction "2_2") (pintype "passive"))
      (node (ref "R74") (pin "1") (pinfunction "1_1") (pintype "passive"))
    )
    (net (code "122") (name "Net-(Q4-B2)") (class "Default")
      (node (ref "Q4") (pin "5") (pinfunction "B2_5") (pintype "passive"))
      (node (ref "R77") (pin "1") (pinfunction "1_1") (pintype "passive"))
    )
    (net (code "123") (name "Net-(Q5-PadE)") (class "Default")
      (node (ref "Q5") (pin "E") (pinfunction "E_E") (pintype "passive"))
      (node (ref "R75") (pin "2") (pinfunction "2_2") (pintype "passive"))
      (node (ref "R76") (pin "2") (pinfunction "2_2") (pintype "passive"))
    )
    (net (code "124") (name "Net-(Q6-B)") (class "Default")
      (node (ref "C32") (pin "+") (pinfunction "+_+") (pintype "passive"))
      (node (ref "Q6") (pin "1") (pinfunction "B_1") (pintype "passive"))
      (node (ref "R79") (pin "1") (pinfunction "1_1") (pintype "passive"))
      (node (ref "R80") (pin "1") (pinfunction "1_1") (pintype "passive"))
    )
    (net (code "125") (name "Net-(R54-Pad2)") (class "Default")
      (node (ref "R54") (pin "2") (pinfunction "2_2") (pintype "passive"))
      (node (ref "R72") (pin "2") (pinfunction "2_2") (pintype "passive"))
    )
    (net (code "126") (name "Net-(R71-Pad1)") (class "Default")
      (node (ref "R71") (pin "1") (pinfunction "1_1") (pintype "passive"))
      (node (ref "R82") (pin "1") (pinfunction "1_1") (pintype "passive"))
      (node (ref "T7") (pin "B") (pinfunction "B_B") (pintype "passive"))
    )
    (net (code "127") (name "Net-(T1-B1)") (class "Default")
      (node (ref "R104") (pin "2") (pinfunction "2_2") (pintype "passive"))
      (node (ref "R28") (pin "1") (pinfunction "1_1") (pintype "passive"))
      (node (ref "T1") (pin "1") (pinfunction "B1_1") (pintype "passive"))
    )
    (net (code "128") (name "Net-(T1-B2)") (class "Default")
      (node (ref "R29") (pin "2") (pinfunction "2_2") (pintype "passive"))
      (node (ref "R30") (pin "2") (pinfunction "2_2") (pintype "passive"))
      (node (ref "T1") (pin "5") (pinfunction "B2_5") (pintype "passive"))
    )
    (net (code "129") (name "Net-(T1-E)") (class "Default")
      (node (ref "R24") (pin "2") (pinfunction "2_2") (pintype "passive"))
      (node (ref "T1") (pin "3") (pinfunction "E_3") (pintype "passive"))
    )
    (net (code "130") (name "Net-(T2-B1)") (class "Default")
      (node (ref "R105") (pin "2") (pinfunction "2_2") (pintype "passive"))
      (node (ref "R32") (pin "1") (pinfunction "1_1") (pintype "passive"))
      (node (ref "T2") (pin "1") (pinfunction "B1_1") (pintype "passive"))
    )
    (net (code "131") (name "Net-(T2-B2)") (class "Default")
      (node (ref "R108") (pin "2") (pinfunction "2_2") (pintype "passive"))
      (node (ref "R26") (pin "1") (pinfunction "1_1") (pintype "passive"))
      (node (ref "T2") (pin "5") (pinfunction "B2_5") (pintype "passive"))
      (node (ref "T3") (pin "1") (pinfunction "B1_1") (pintype "passive"))
    )
    (net (code "132") (name "Net-(T2-E)") (class "Default")
      (node (ref "R31") (pin "1") (pinfunction "1_1") (pintype "passive"))
      (node (ref "T2") (pin "3") (pinfunction "E_3") (pintype "passive"))
    )
    (net (code "133") (name "Net-(T3-B2)") (class "Default")
      (node (ref "R109") (pin "2") (pinfunction "2_2") (pintype "passive"))
      (node (ref "R36") (pin "1") (pinfunction "1_1") (pintype "passive"))
      (node (ref "T3") (pin "5") (pinfunction "B2_5") (pintype "passive"))
    )
    (net (code "134") (name "Net-(T3-E)") (class "Default")
      (node (ref "R35") (pin "1") (pinfunction "1_1") (pintype "passive"))
      (node (ref "T3") (pin "3") (pinfunction "E_3") (pintype "passive"))
    )
    (net (code "135") (name "Net-(T4-B1)") (class "Default")
      (node (ref "R39") (pin "1") (pinfunction "1_1") (pintype "passive"))
      (node (ref "R95") (pin "2") (pinfunction "2_2") (pintype "passive"))
      (node (ref "T4") (pin "1") (pinfunction "B1_1") (pintype "passive"))
    )
    (net (code "136") (name "Net-(T4-B2)") (class "Default")
      (node (ref "R103") (pin "2") (pinfunction "2_2") (pintype "passive"))
      (node (ref "R42") (pin "1") (pinfunction "1_1") (pintype "passive"))
      (node (ref "T4") (pin "5") (pinfunction "B2_5") (pintype "passive"))
    )
    (net (code "137") (name "Net-(T4-E)") (class "Default")
      (node (ref "R38") (pin "1") (pinfunction "1_1") (pintype "passive"))
      (node (ref "R41") (pin "2") (pinfunction "2_2") (pintype "passive"))
      (node (ref "T4") (pin "3") (pinfunction "E_3") (pintype "passive"))
    )
    (net (code "138") (name "VDD") (class "Default")
      (node (ref "IC1") (pin "14") (pinfunction "VDD_14") (pintype "power_in"))
      (node (ref "IC10") (pin "4") (pinfunction "V+_4") (pintype "power_in"))
      (node (ref "IC11") (pin "11") (pinfunction "V+_11") (pintype "power_in"))
      (node (ref "IC12") (pin "11") (pinfunction "V+_11") (pintype "power_in"))
      (node (ref "IC13") (pin "14") (pinfunction "VDD_14") (pintype "power_in"))
      (node (ref "IC14") (pin "8") (pinfunction "V+_8") (pintype "power_in"))
      (node (ref "IC15") (pin "8") (pinfunction "V+_8") (pintype "power_in"))
      (node (ref "IC16") (pin "8") (pinfunction "V+_8") (pintype "power_in"))
      (node (ref "IC17") (pin "8") (pinfunction "V+_8") (pintype "power_in"))
      (node (ref "IC2") (pin "14") (pinfunction "VDD_14") (pintype "power_in"))
      (node (ref "IC3") (pin "13") (pinfunction "I_13") (pintype "input"))
      (node (ref "IC3") (pin "14") (pinfunction "VDD_14") (pintype "power_in"))
      (node (ref "IC4") (pin "8") (pinfunction "V+_8") (pintype "power_in"))
      (node (ref "IC5") (pin "8") (pinfunction "V+_8") (pintype "power_in"))
      (node (ref "IC6") (pin "8") (pinfunction "V+_8") (pintype "power_in"))
      (node (ref "IC7") (pin "8") (pinfunction "V+_8") (pintype "power_in"))
      (node (ref "IC8") (pin "4") (pinfunction "V+_4") (pintype "power_in"))
      (node (ref "IC9") (pin "16") (pinfunction "VCC_16") (pintype "power_in"))
      (node (ref "Q5") (pin "B") (pinfunction "B_B") (pintype "passive"))
      (node (ref "Q6") (pin "2") (pinfunction "C_2") (pintype "passive"))
      (node (ref "R16") (pin "2") (pinfunction "2_2") (pintype "passive"))
      (node (ref "R17") (pin "2") (pinfunction "2_2") (pintype "passive"))
      (node (ref "R21") (pin "2") (pinfunction "2_2") (pintype "passive"))
      (node (ref "R25") (pin "2") (pinfunction "2_2") (pintype "passive"))
      (node (ref "R30") (pin "1") (pinfunction "1_1") (pintype "passive"))
      (node (ref "R31") (pin "2") (pinfunction "2_2") (pintype "passive"))
      (node (ref "R32") (pin "2") (pinfunction "2_2") (pintype "passive"))
      (node (ref "R35") (pin "2") (pinfunction "2_2") (pintype "passive"))
      (node (ref "R36") (pin "2") (pinfunction "2_2") (pintype "passive"))
      (node (ref "R38") (pin "2") (pinfunction "2_2") (pintype "passive"))
      (node (ref "R39") (pin "2") (pinfunction "2_2") (pintype "passive"))
      (node (ref "R48") (pin "2") (pinfunction "2_2") (pintype "passive"))
      (node (ref "R49") (pin "1") (pinfunction "1_1") (pintype "passive"))
      (node (ref "R50") (pin "2") (pinfunction "2_2") (pintype "passive"))
      (node (ref "R65") (pin "1") (pinfunction "1_1") (pintype "passive"))
      (node (ref "R66") (pin "1") (pinfunction "1_1") (pintype "passive"))
      (node (ref "R70") (pin "2") (pinfunction "2_2") (pintype "passive"))
      (node (ref "R73") (pin "2") (pinfunction "2_2") (pintype "passive"))
      (node (ref "R79") (pin "2") (pinfunction "2_2") (pintype "passive"))
      (node (ref "R82") (pin "2") (pinfunction "2_2") (pintype "passive"))
      (node (ref "T5") (pin "C") (pinfunction "C_C") (pintype "passive"))
      (node (ref "T6") (pin "C") (pinfunction "C_C") (pintype "passive"))
    )
    (net (code "139") (name "VSS") (class "Default")
      (node (ref "C6") (pin "-") (pinfunction "-_-") (pintype "passive"))
      (node (ref "IC10") (pin "11") (pinfunction "V-_11") (pintype "power_in"))
      (node (ref "IC11") (pin "6") (pinfunction "V-_6") (pintype "power_in"))
      (node (ref "IC12") (pin "6") (pinfunction "V-_6") (pintype "power_in"))
      (node (ref "IC14") (pin "4") (pinfunction "V-_4") (pintype "power_in"))
      (node (ref "IC15") (pin "4") (pinfunction "V-_4") (pintype "power_in"))
      (node (ref "IC16") (pin "4") (pinfunction "V-_4") (pintype "power_in"))
      (node (ref "IC17") (pin "4") (pinfunction "V-_4") (pintype "power_in"))
      (node (ref "IC6") (pin "4") (pinfunction "V-_4") (pintype "power_in"))
      (node (ref "IC7") (pin "4") (pinfunction "V-_4") (pintype "power_in"))
      (node (ref "IC8") (pin "11") (pinfunction "V-_11") (pintype "power_in"))
      (node (ref "IC9") (pin "7") (pinfunction "VEE_7") (pintype "power_in"))
      (node (ref "R44") (pin "1") (pinfunction "1_1") (pintype "passive"))
      (node (ref "R45") (pin "1") (pinfunction "1_1") (pintype "passive"))
      (node (ref "T1") (pin "2") (pinfunction "C1_2") (pintype "passive"))
      (node (ref "T2") (pin "4") (pinfunction "C2_4") (pintype "passive"))
      (node (ref "T3") (pin "4") (pinfunction "C2_4") (pintype "passive"))
      (node (ref "T4") (pin "4") (pinfunction "C2_4") (pintype "passive"))
    )
    (net (code "140") (name "unconnected-(C6-Pad+)") (class "Default")
      (node (ref "C6") (pin "+") (pinfunction "+_+") (pintype "passive"))
    )
    (net (code "141") (name "unconnected-(IC2B-A-Pad11)") (class "Default")
      (node (ref "IC2") (pin "11") (pinfunction "A_11") (pintype "tri_state"))
    )
    (net (code "142") (name "unconnected-(IC2B-B-Pad10)") (class "Default")
      (node (ref "IC2") (pin "10") (pinfunction "B_10") (pintype "tri_state"))
    )
    (net (code "143") (name "unconnected-(IC3D-O-Pad8)") (class "Default")
      (node (ref "IC3") (pin "8") (pinfunction "O_8") (pintype "output"))
    )
    (net (code "144") (name "unconnected-(IC3E-O-Pad10)") (class "Default")
      (node (ref "IC3") (pin "10") (pinfunction "O_10") (pintype "output"))
    )
    (net (code "145") (name "unconnected-(IC11A-BUFF{slash}IN-Pad7)") (class "Default")
      (node (ref "IC11") (pin "7") (pinfunction "BUFF/IN_7") (pintype "input"))
    )
    (net (code "146") (name "unconnected-(IC11A-BUFF{slash}OUT-Pad8)") (class "Default")
      (node (ref "IC11") (pin "8") (pinfunction "BUFF/OUT_8") (pintype "output"))
    )
    (net (code "147") (name "unconnected-(IC11A-DIODE{slash}BIAS-Pad2)") (class "Default")
      (node (ref "IC11") (pin "2") (pinfunction "DIODE/BIAS_2") (pintype "passive"))
    )
    (net (code "148") (name "unconnected-(IC11B-BUFF{slash}IN-Pad10)") (class "Default")
      (node (ref "IC11") (pin "10") (pinfunction "BUFF/IN_10") (pintype "input"))
    )
    (net (code "149") (name "unconnected-(IC11B-BUFF{slash}OUT-Pad9)") (class "Default")
      (node (ref "IC11") (pin "9") (pinfunction "BUFF/OUT_9") (pintype "output"))
    )
    (net (code "150") (name "unconnected-(IC11B-DIODE{slash}BIAS-Pad15)") (class "Default")
      (node (ref "IC11") (pin "15") (pinfunction "DIODE/BIAS_15") (pintype "passive"))
    )
    (net (code "151") (name "unconnected-(IC12A-DIODE{slash}BIAS-Pad2)") (class "Default")
      (node (ref "IC12") (pin "2") (pinfunction "DIODE/BIAS_2") (pintype "passive"))
    )
    (net (code "152") (name "unconnected-(IC12B-DIODE{slash}BIAS-Pad15)") (class "Default")
      (node (ref "IC12") (pin "15") (pinfunction "DIODE/BIAS_15") (pintype "passive"))
    )
    (net (code "153") (name "unconnected-(IC13B-B-Pad10)") (class "Default")
      (node (ref "IC13") (pin "10") (pinfunction "B_10") (pintype "tri_state"))
    )
    (net (code "154") (name "unconnected-(Q5-PadC)") (class "Default")
      (node (ref "Q5") (pin "C") (pinfunction "C_C") (pintype "passive"))
    )
    (net (code "155") (name "unconnected-(R60-Pad2)") (class "Default")
      (node (ref "R60") (pin "2") (pinfunction "2_2") (pintype "passive"))
    )
    (net (code "156") (name "unconnected-(R74-Pad2)") (class "Default")
      (node (ref "R74") (pin "2") (pinfunction "2_2") (pintype "passive"))
    )
    (net (code "157") (name "unconnected-(T7-PadC)") (class "Default")
      (node (ref "T7") (pin "C") (pinfunction "C_C") (pintype "passive"))
    )
  )
)
